# SCH_CyBorg.net
KiCad netlist of a schematic drawn in EasyEDA
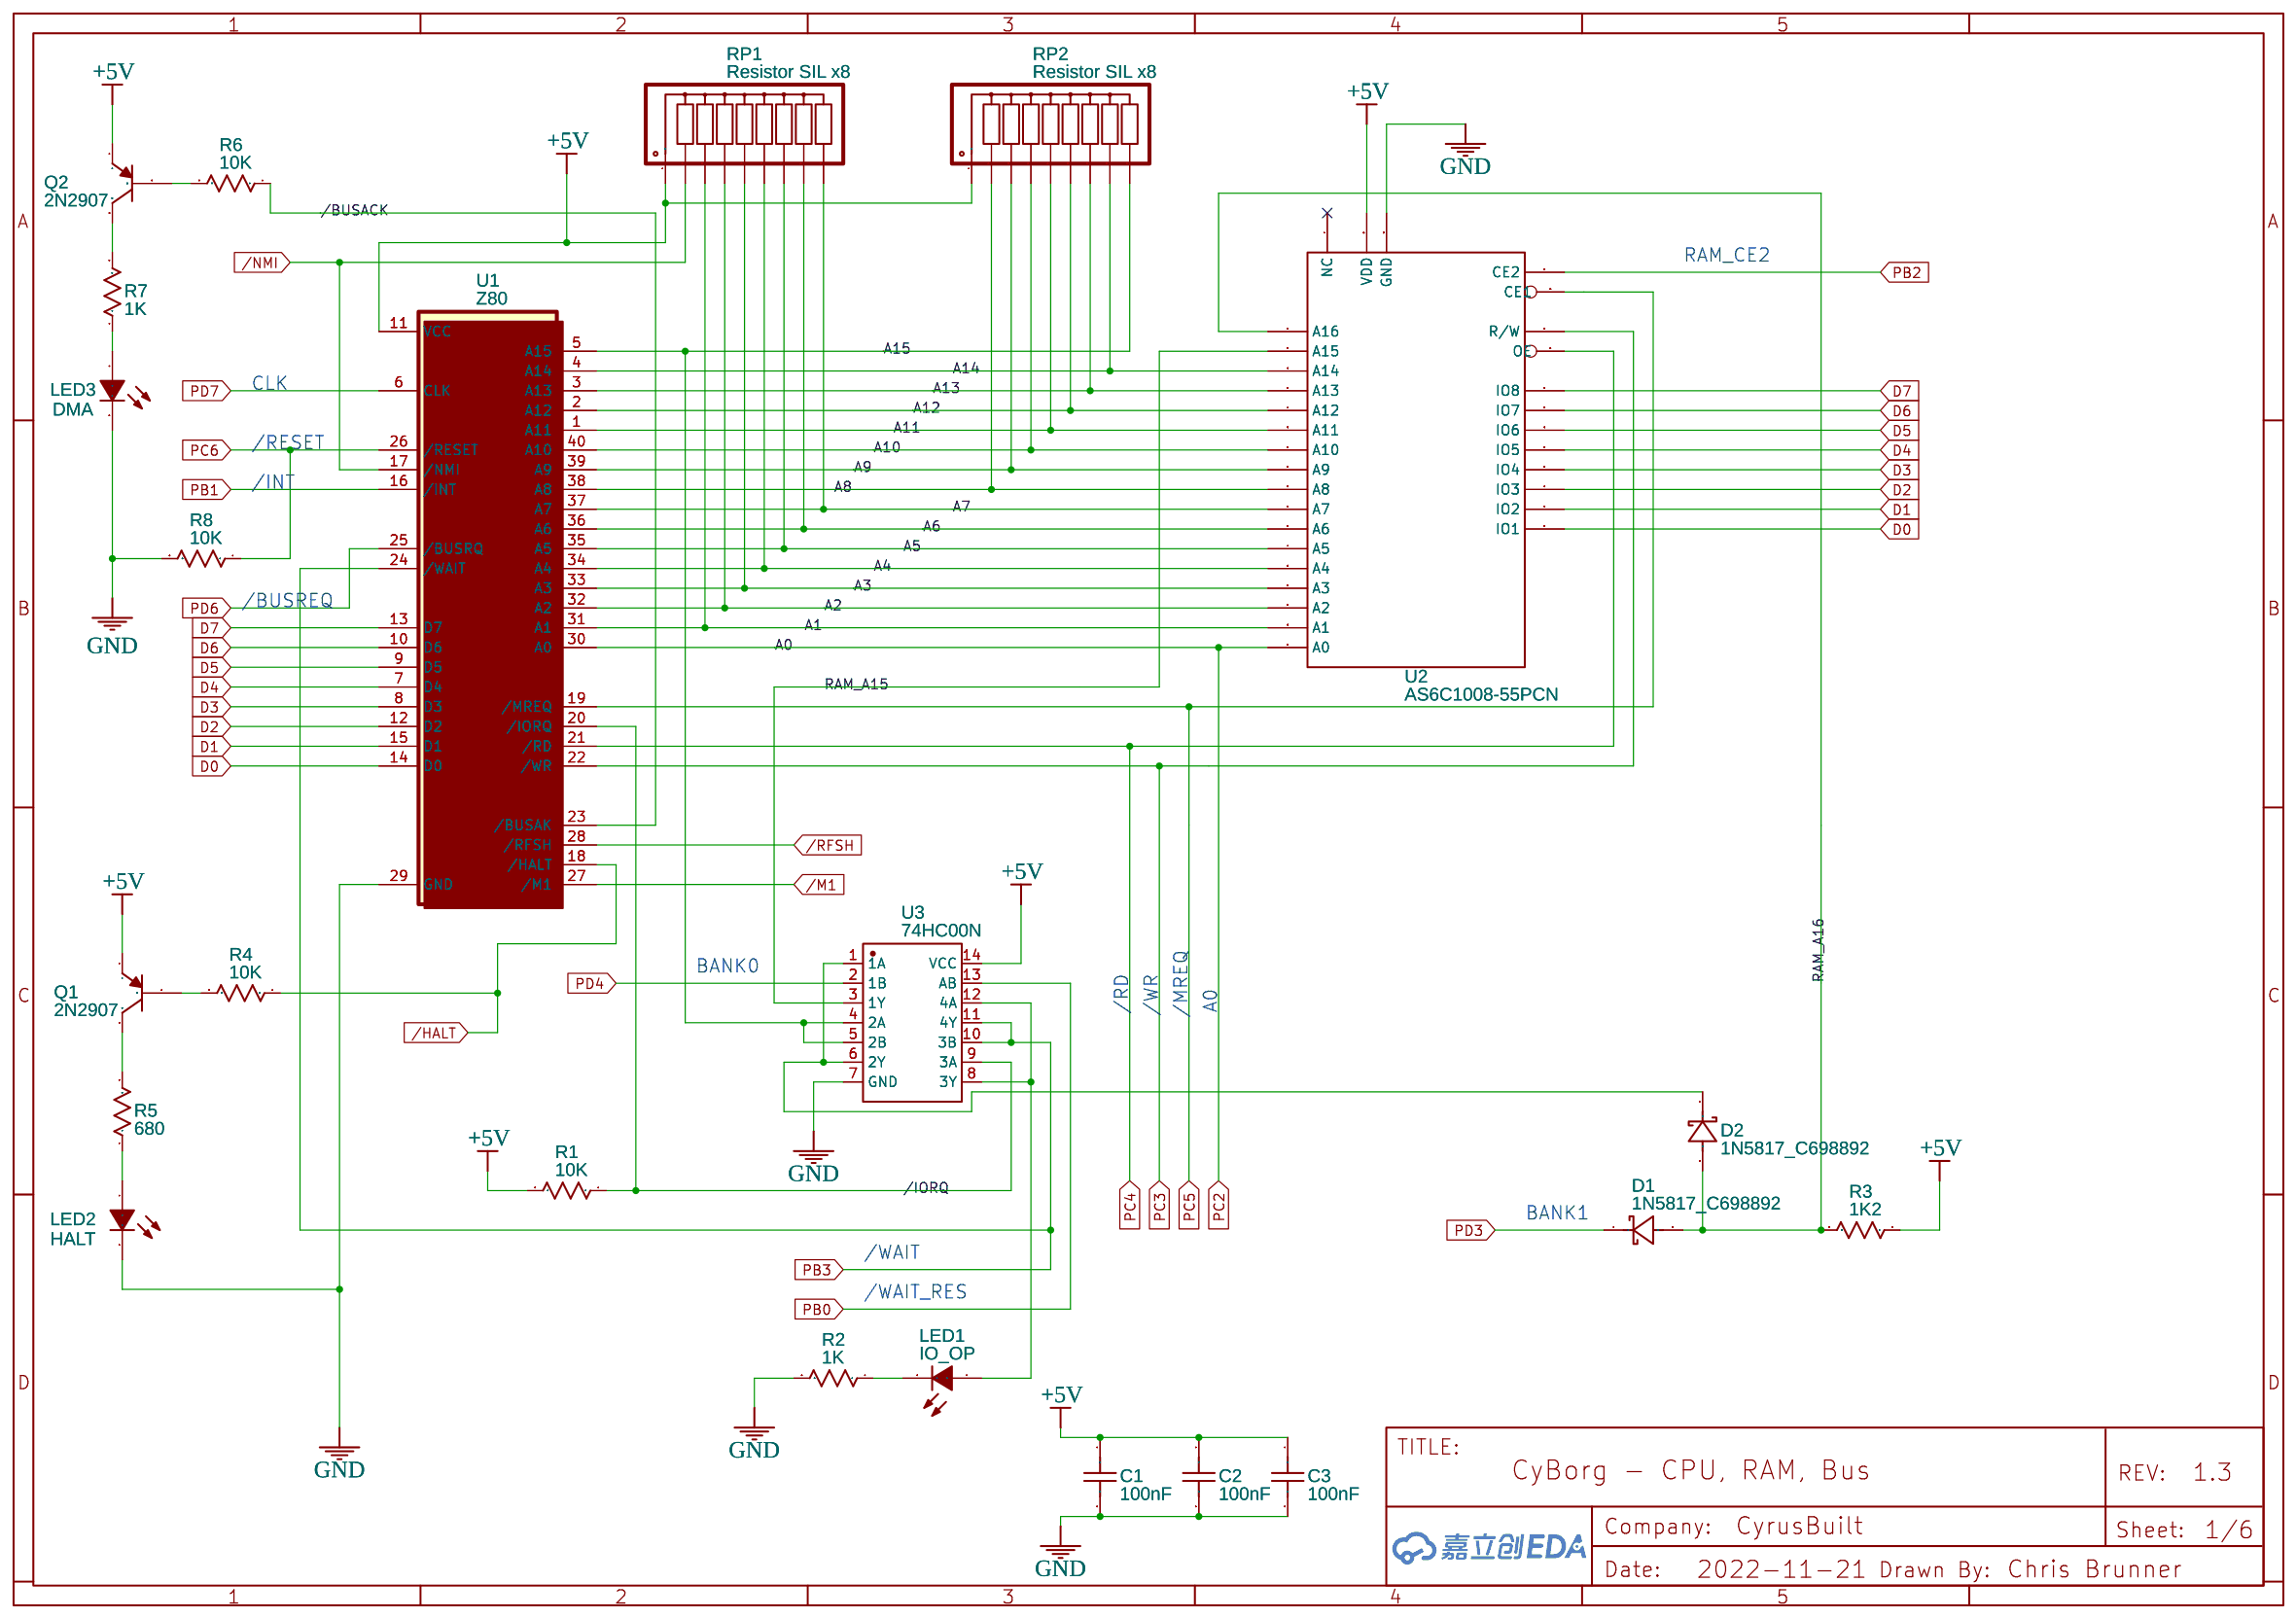
[diagram p0: CPU]
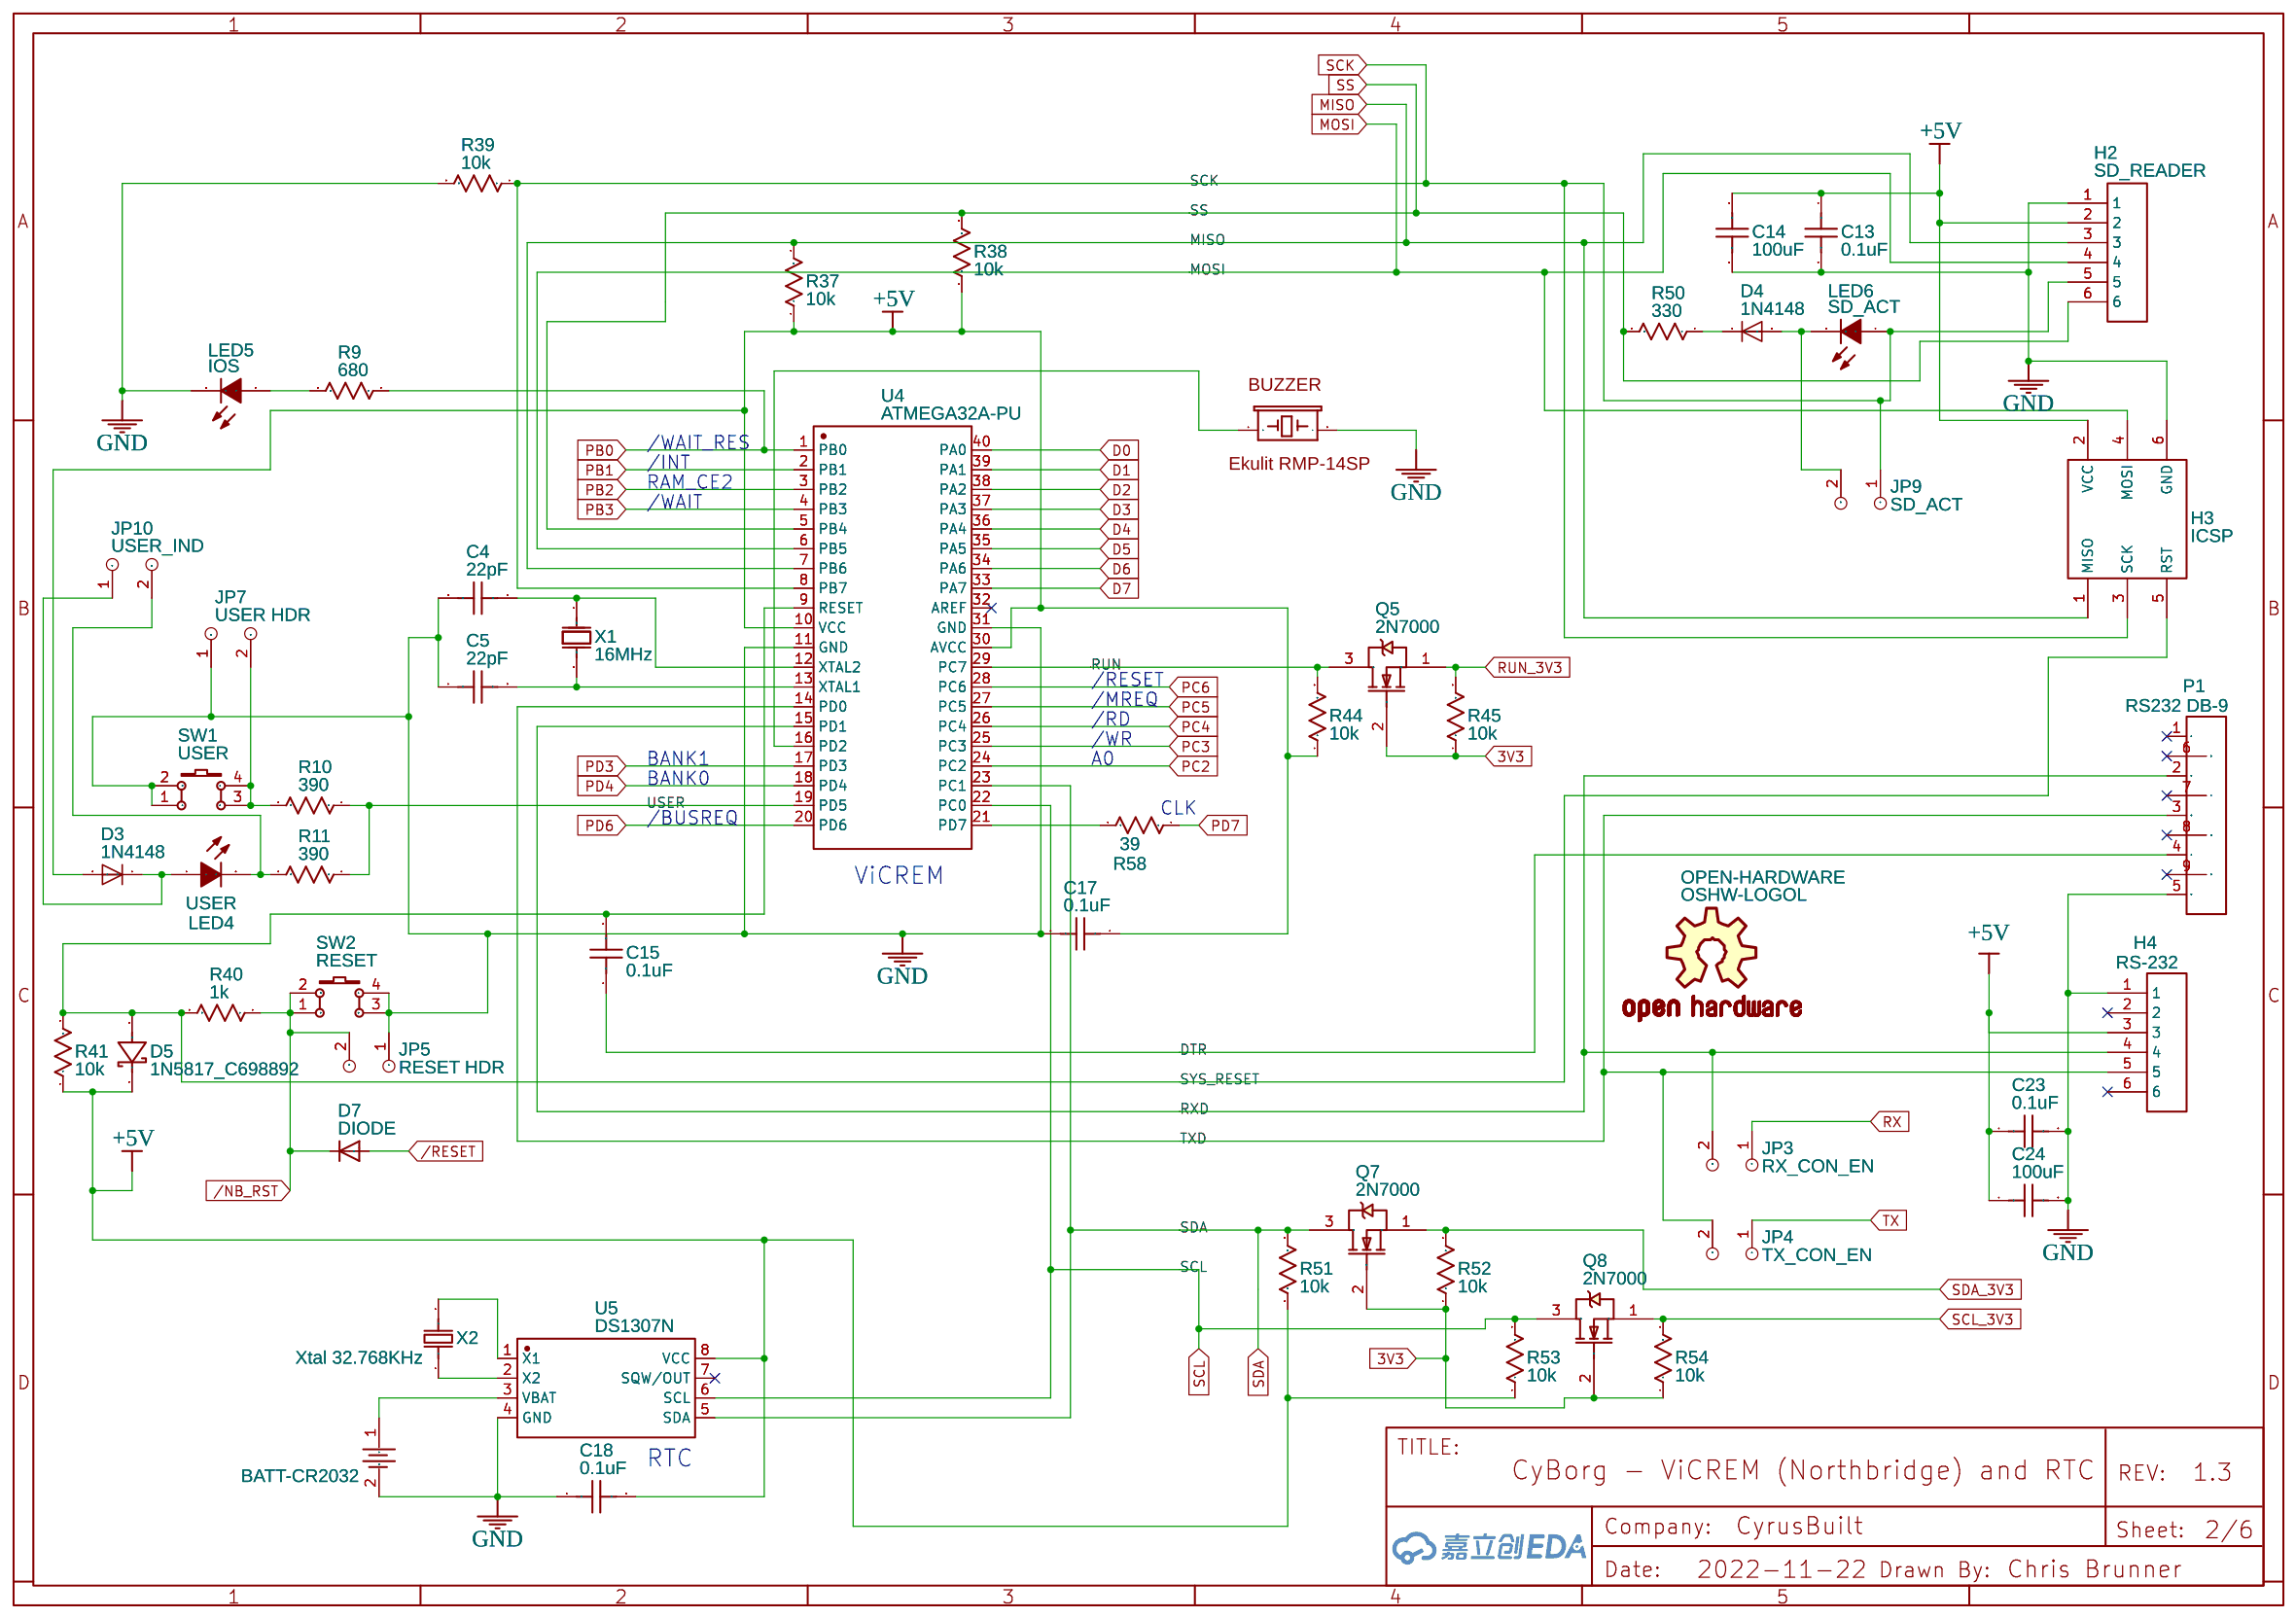
[diagram p1: ViCREM]
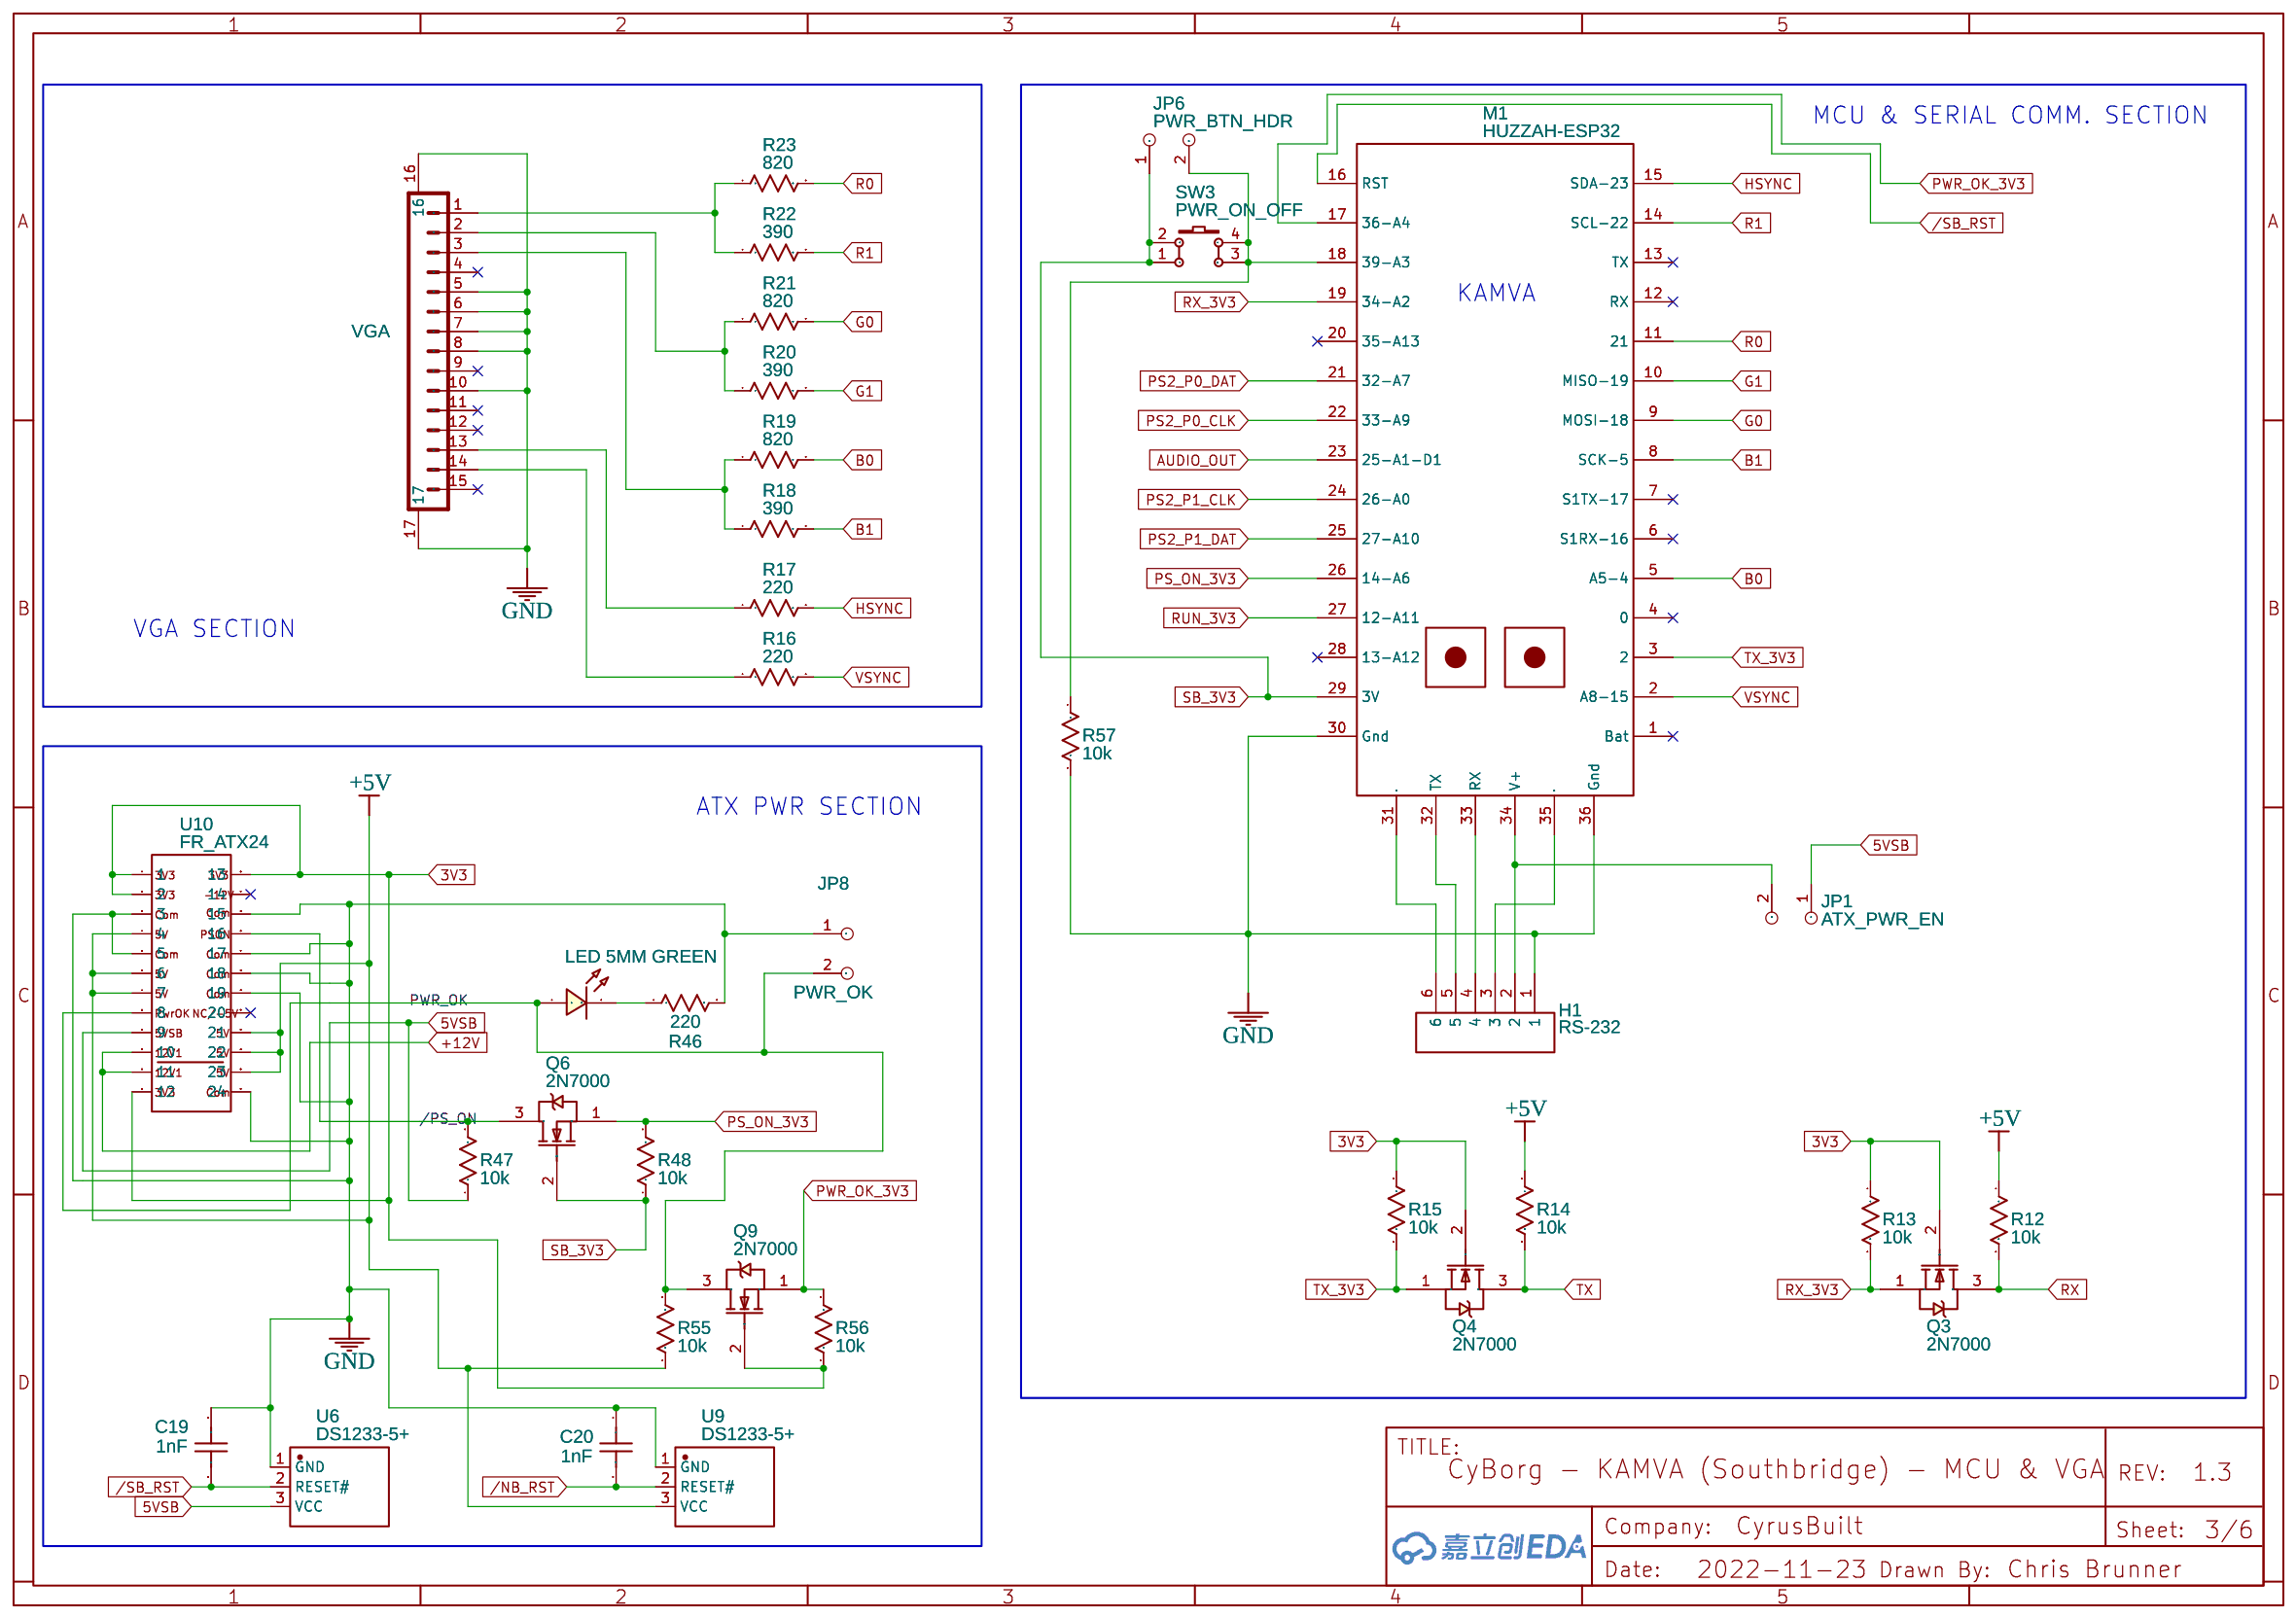
[diagram p2: KAMVA - P1]
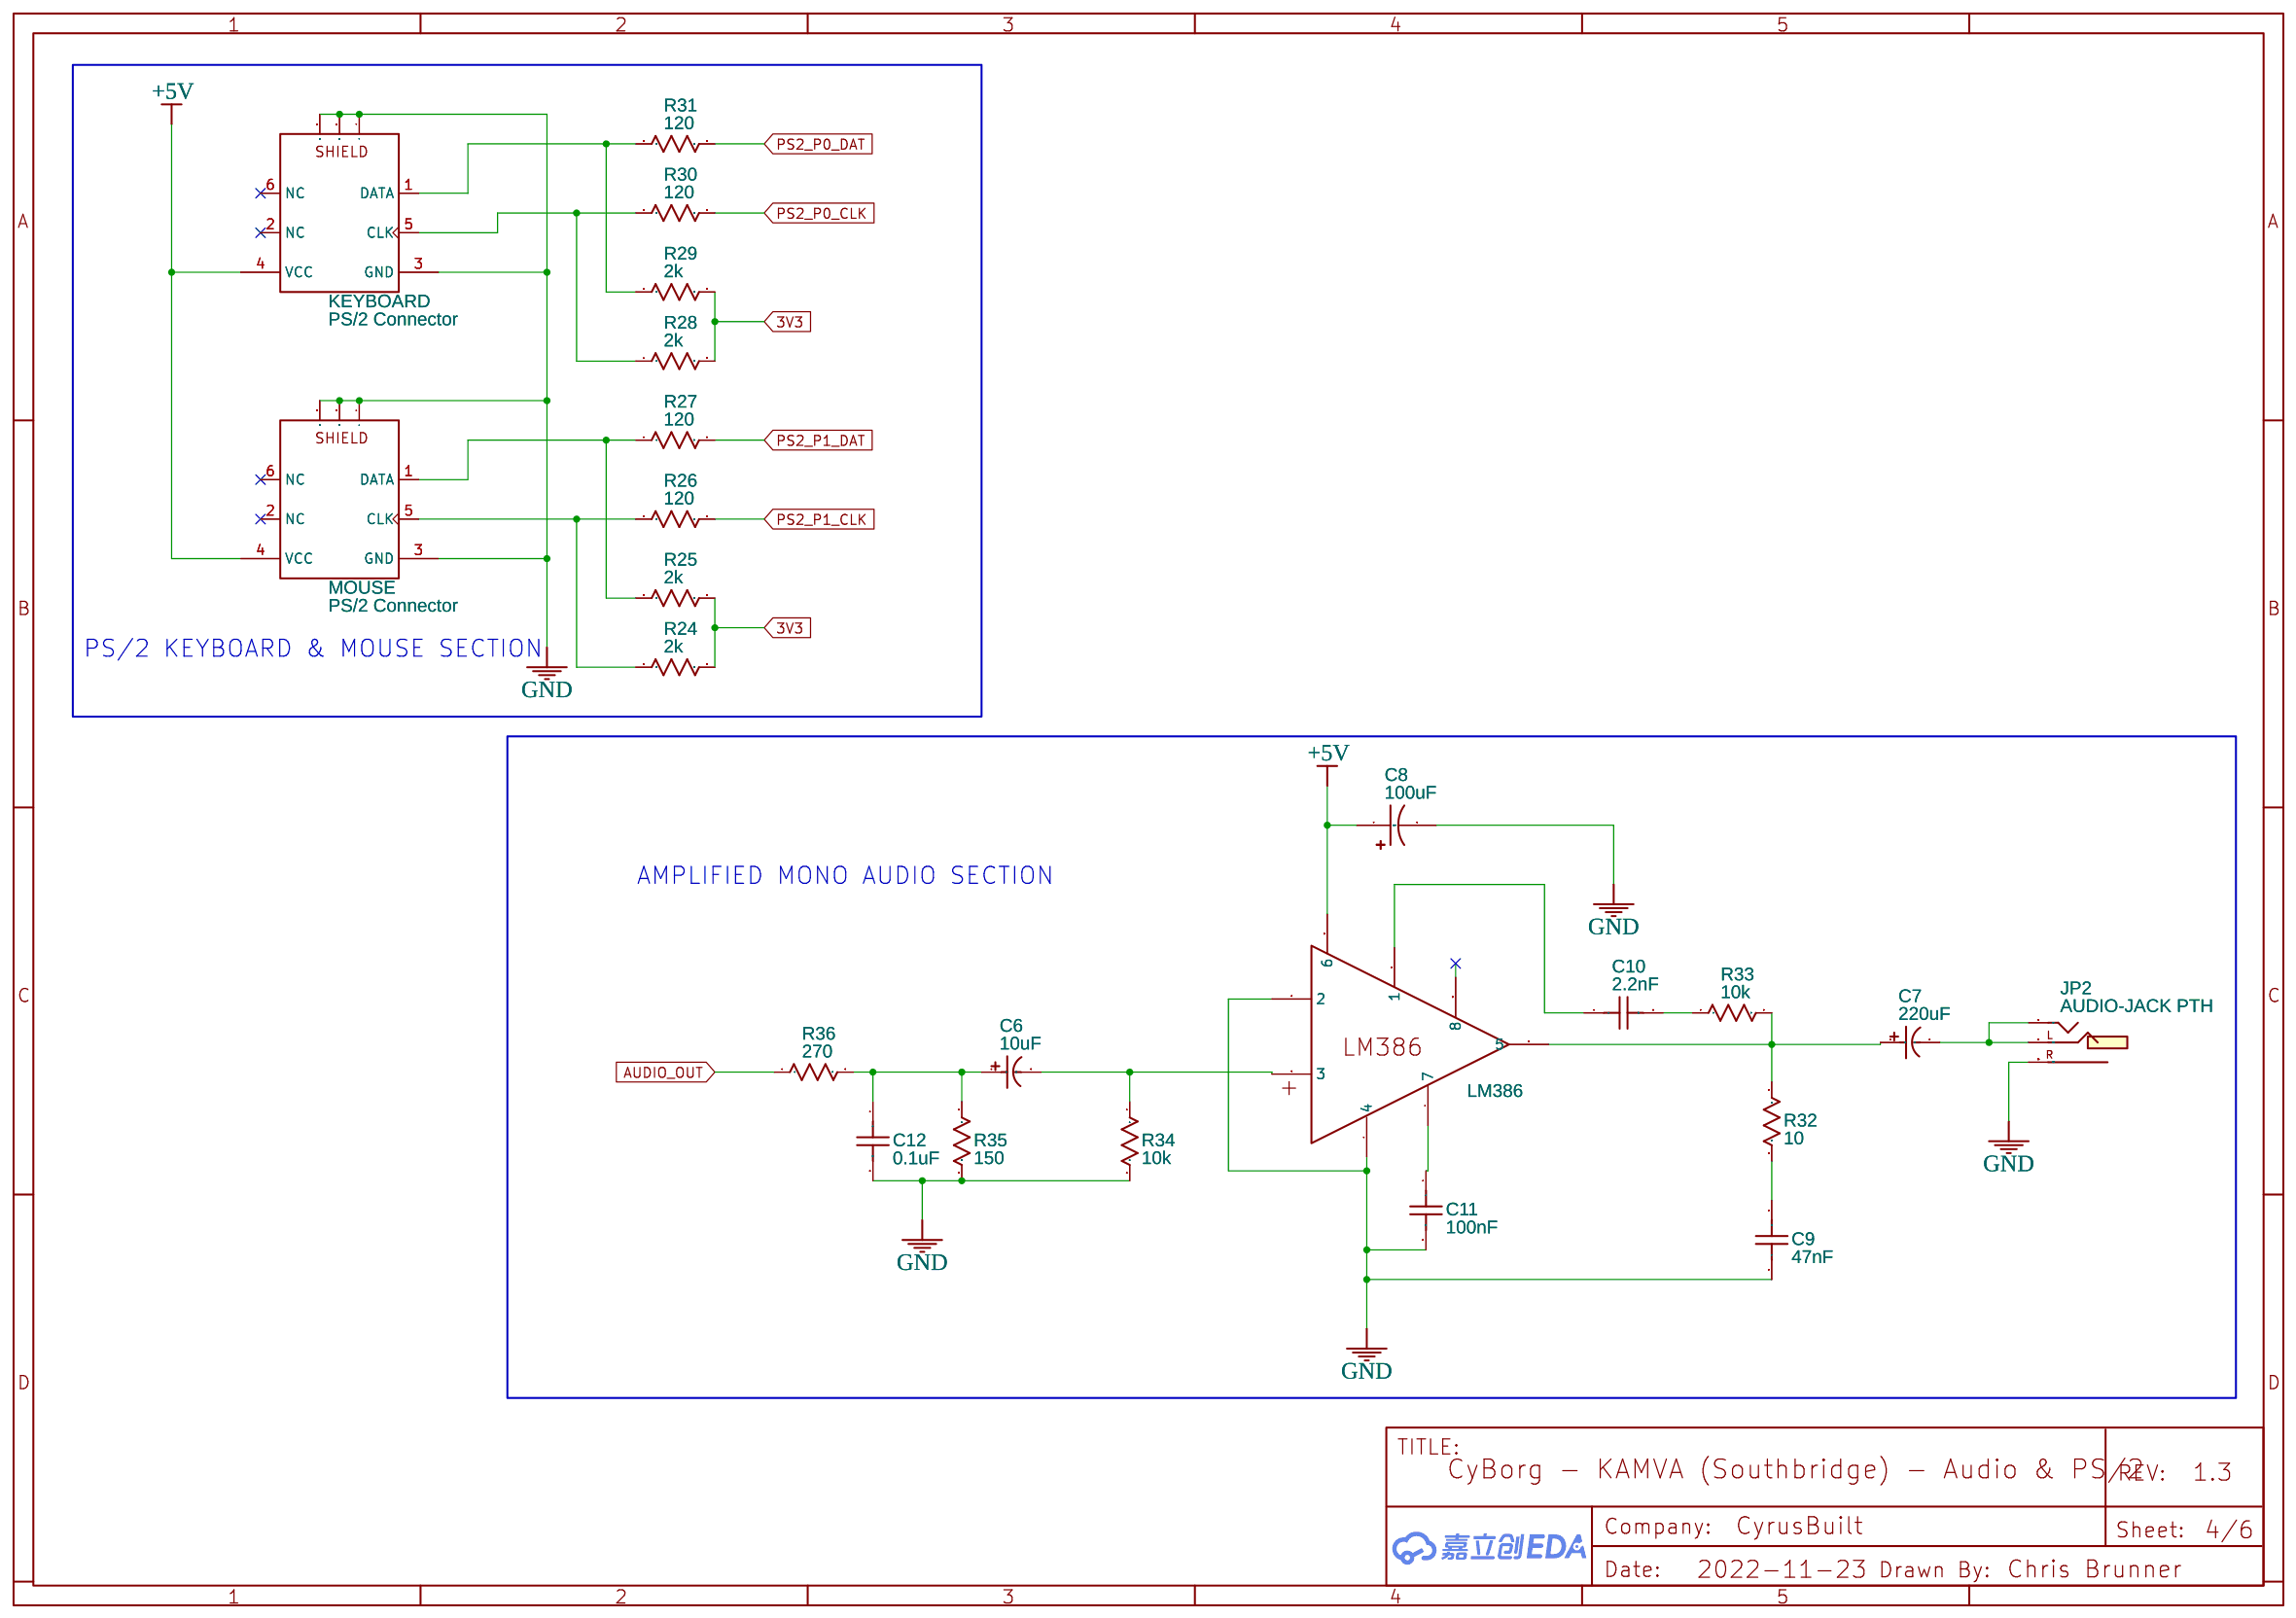
[diagram p3: KAMVA - P2]
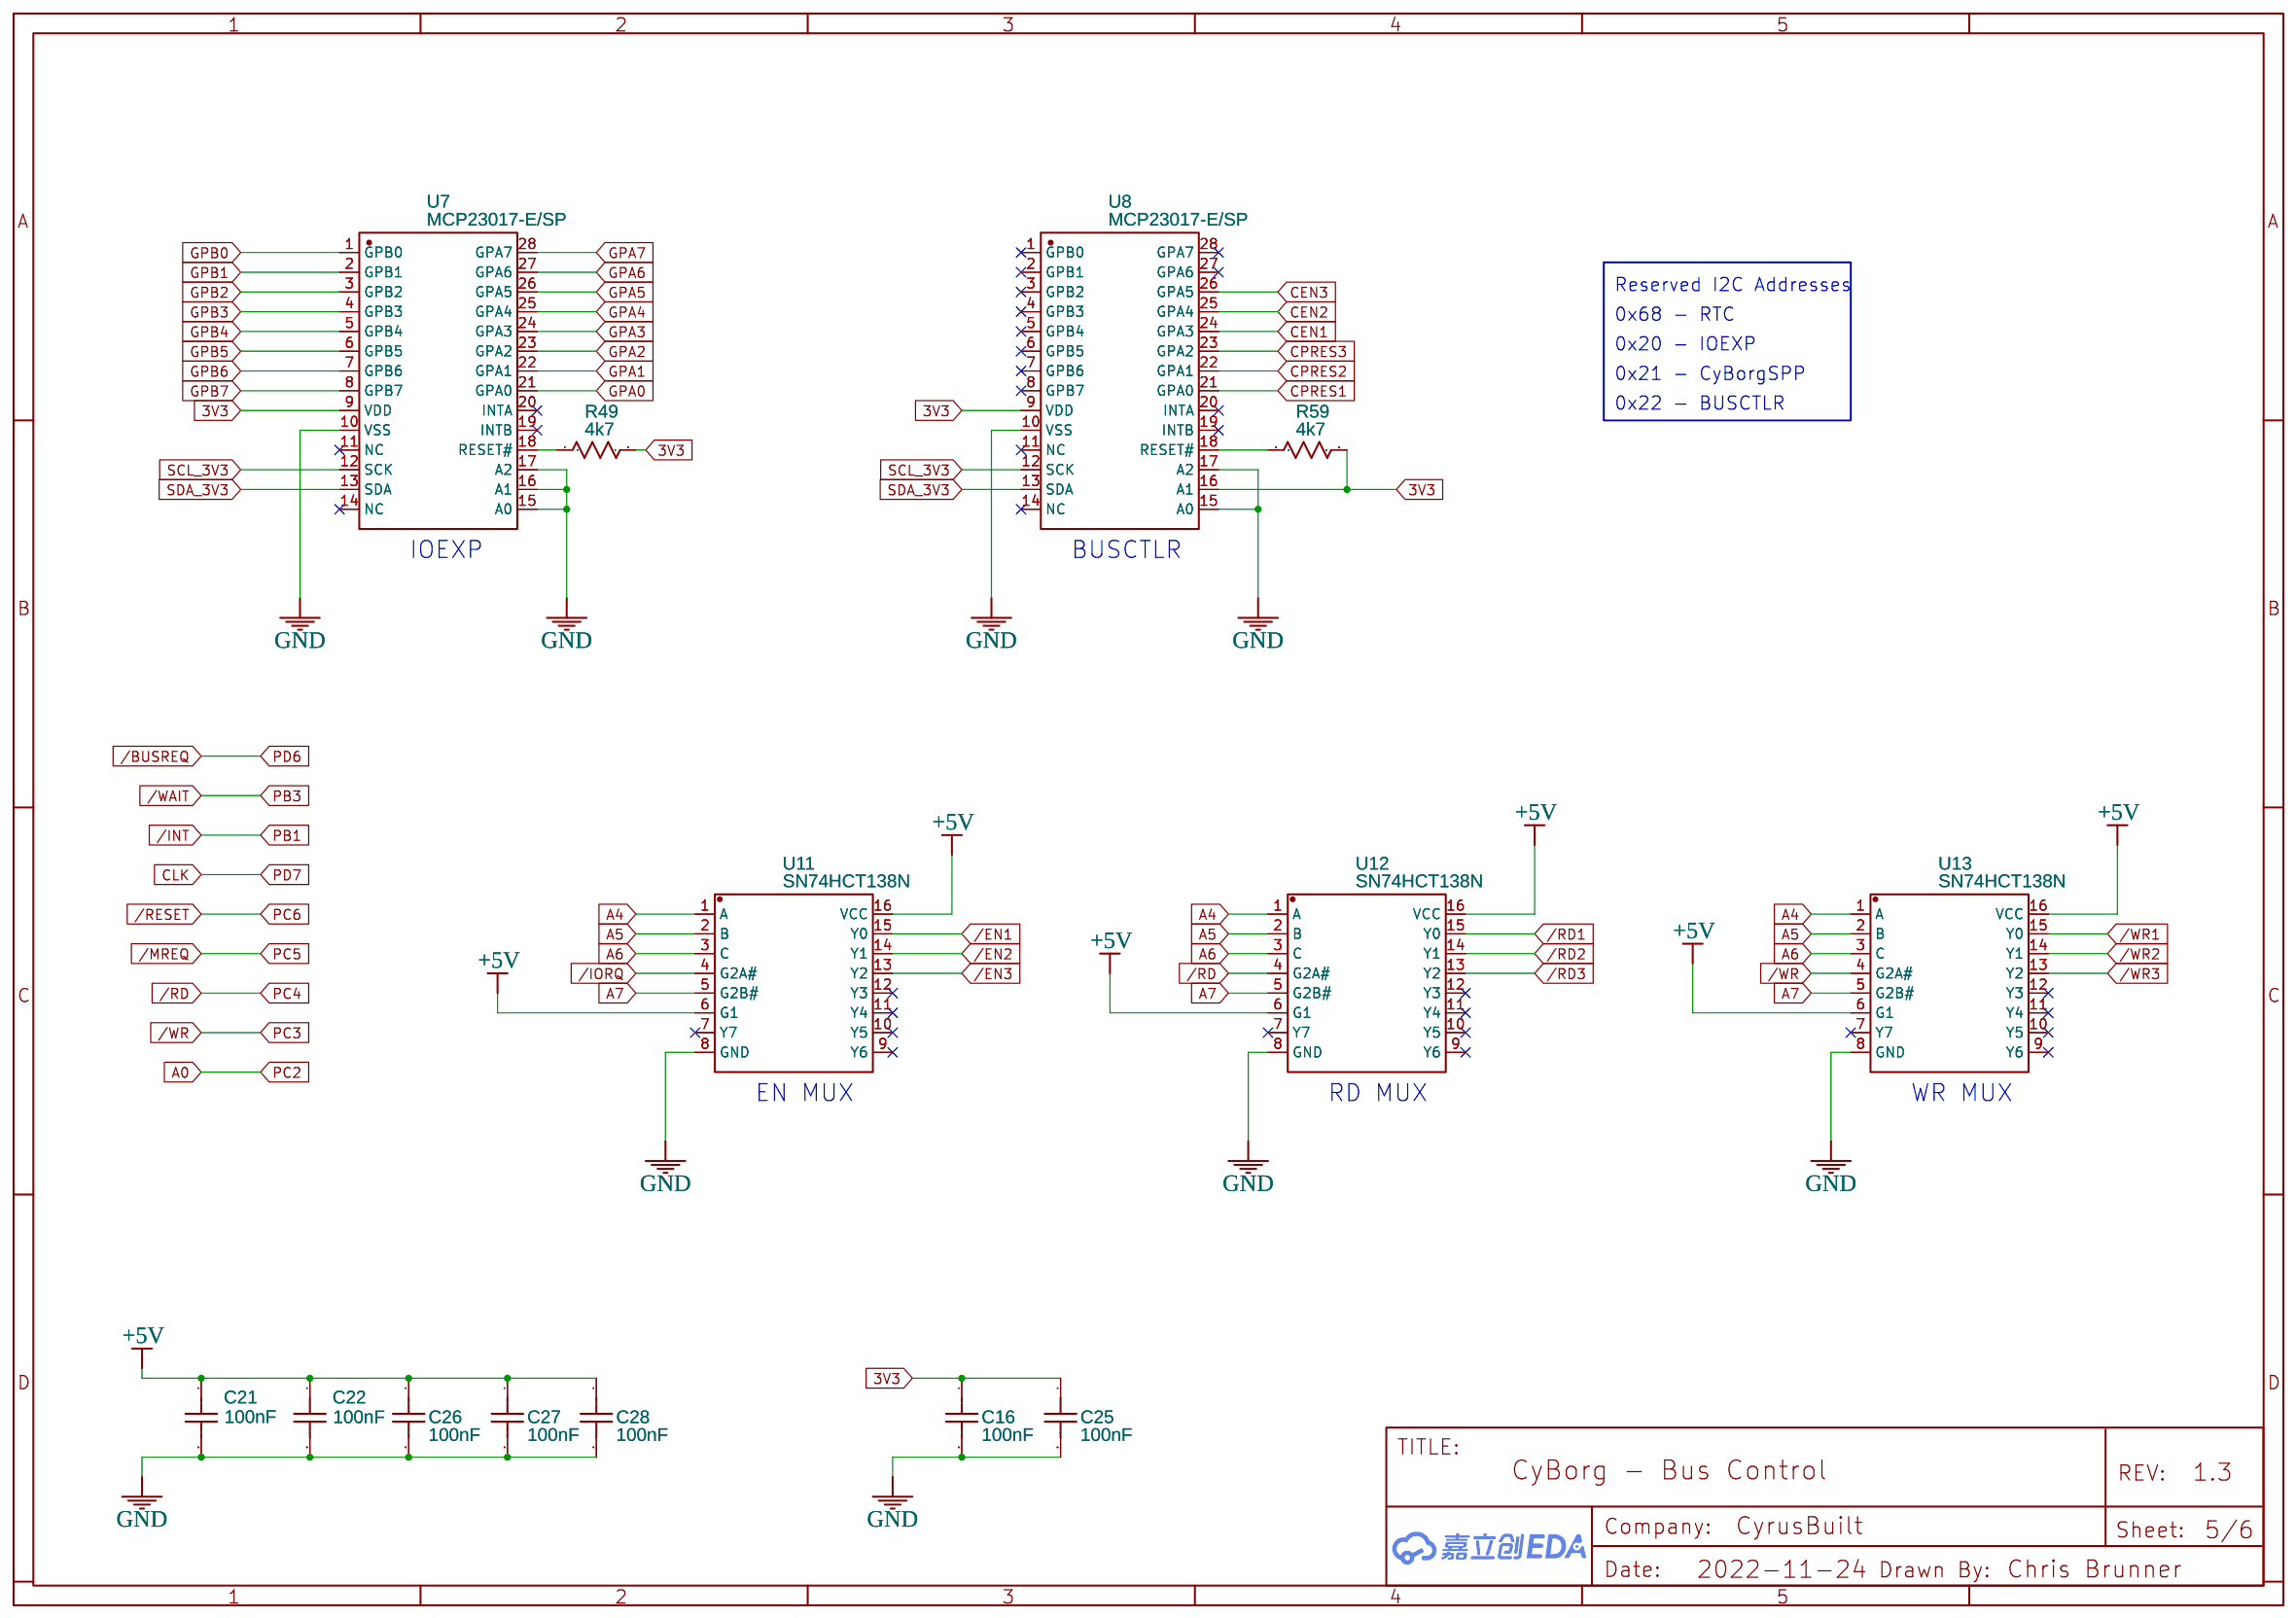
[diagram p4: Bus Control]
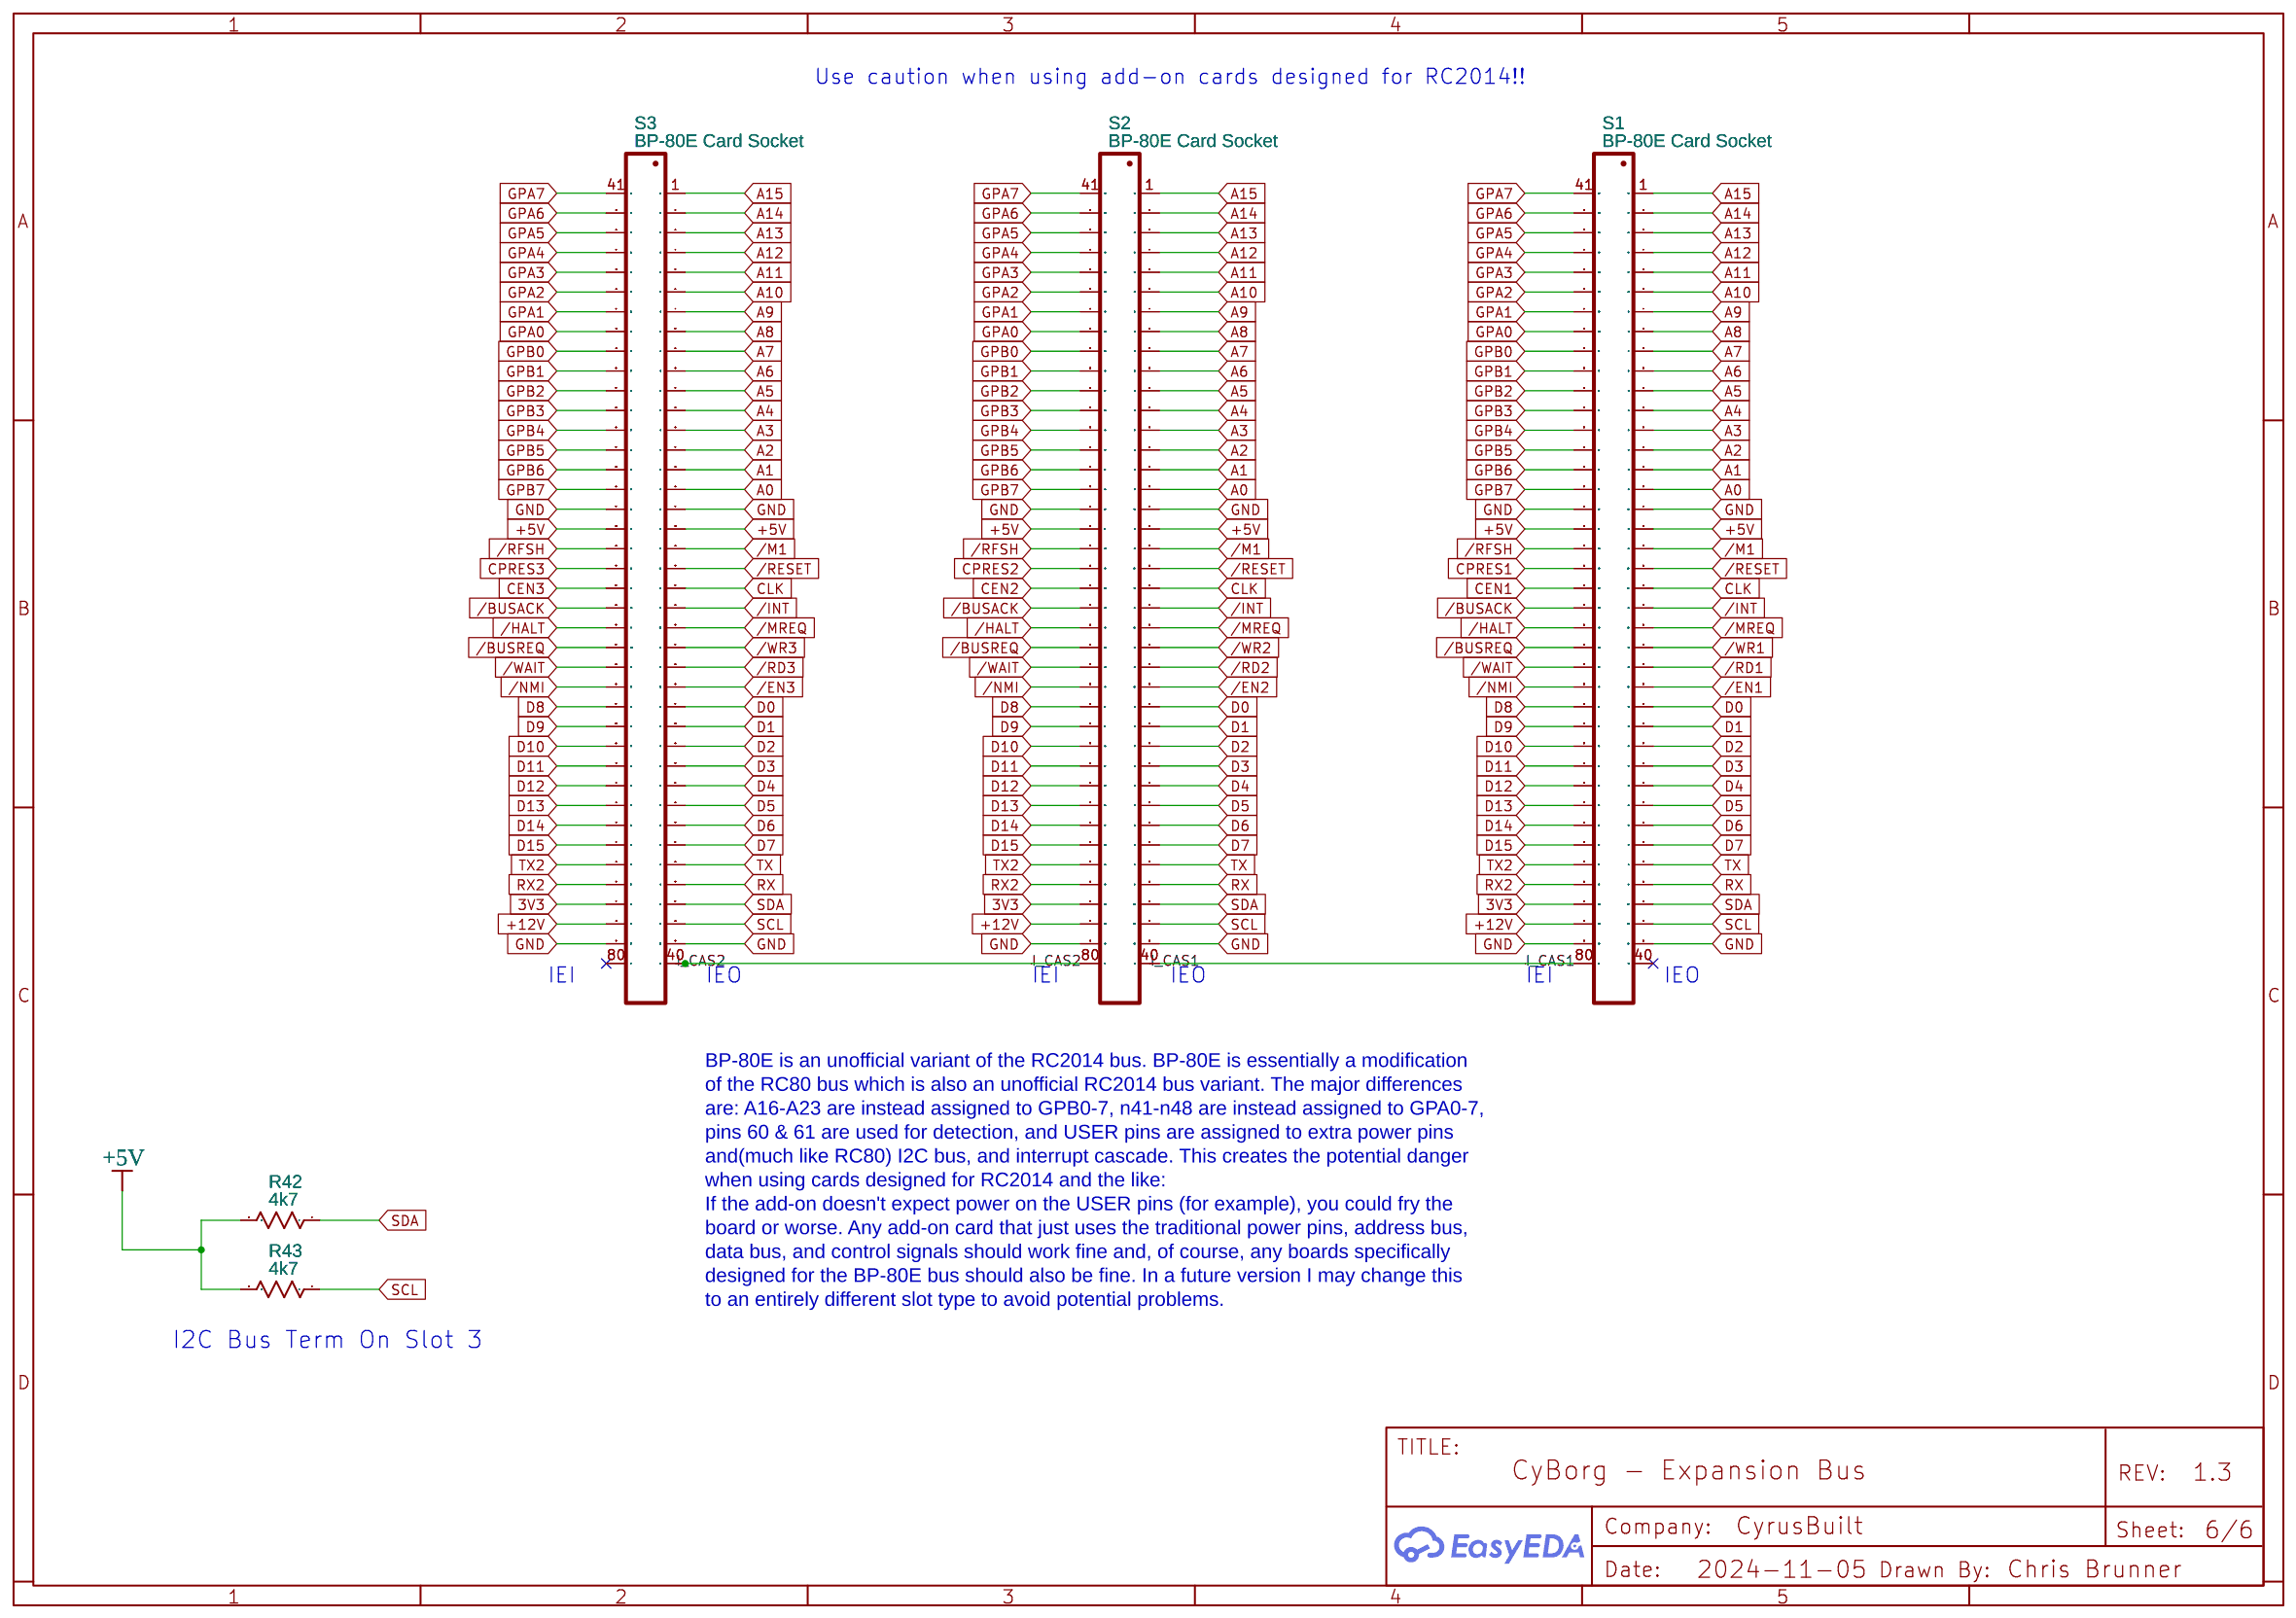
[diagram p5: Expansion Bus]

(export (version "E")
  (design (tool "Eeschema 10.0.6"))
  (components
    (comp (ref "C1") (value "100nF") (libsource (lib "") (part "C_0603_US")))
    (comp (ref "C2") (value "100nF") (libsource (lib "") (part "C_0603_US")))
    (comp (ref "C3") (value "100nF") (libsource (lib "") (part "C_0603_US")))
    (comp (ref "D1")
      (value "1N5817_C698892")
      (fields (field (name "Manufacturer Part") "1N5817") (field (name "Manufacturer") "YANGJIE(扬杰)"))
      (libsource (lib "") (part "1N5817_C698892"))
    )
    (comp (ref "D2")
      (value "1N5817_C698892")
      (fields (field (name "Manufacturer Part") "1N5817") (field (name "Manufacturer") "YANGJIE(扬杰)"))
      (libsource (lib "") (part "1N5817_C698892_1"))
    )
    (comp (ref "LED1")
      (value "IO_OP")
      (fields
        (field (name "Manufacturer Part") "204-10SURD/S530-A3")
        (field (name "Manufacturer") "EVERLIGHT(亿光)")
      )
      (libsource (lib "") (part "204-10SURD/S530-A3"))
    )
    (comp (ref "LED2")
      (value "HALT")
      (fields
        (field (name "Manufacturer Part") "204-10SURD/S530-A3")
        (field (name "Manufacturer") "EVERLIGHT(亿光)")
      )
      (libsource (lib "") (part "204-10SURD/S530-A3_1"))
    )
    (comp (ref "LED3")
      (value "DMA")
      (fields
        (field (name "Manufacturer Part") "204-10SURD/S530-A3")
        (field (name "Manufacturer") "EVERLIGHT(亿光)")
      )
      (libsource (lib "") (part "204-10SURD/S530-A3_1"))
    )
    (comp (ref "Q1")
      (value "2N2907")
      (fields (field (name "Manufacturer Part") "2N2907A") (field (name "Manufacturer") "ST(先科)"))
      (libsource (lib "") (part "2N2907"))
    )
    (comp (ref "Q2")
      (value "2N2907")
      (fields (field (name "Manufacturer Part") "2N2907A") (field (name "Manufacturer") "ST(先科)"))
      (libsource (lib "") (part "2N2907"))
    )
    (comp (ref "R1")
      (value "10K")
      (fields (field (name "Manufacturer Part") "MCF 0.25W 150R") (field (name "Manufacturer") "MULTICOMP"))
      (libsource (lib "") (part "MCF 0.25W 150R"))
    )
    (comp (ref "R2")
      (value "1K")
      (fields (field (name "Manufacturer Part") "MCF 0.25W 1K") (field (name "Manufacturer") "MULTICOMP"))
      (libsource (lib "") (part "MCF 0.25W 150R"))
    )
    (comp (ref "R3")
      (value "1K2")
      (fields (field (name "Manufacturer Part") "MCF 0.25W 150R") (field (name "Manufacturer") "MULTICOMP"))
      (libsource (lib "") (part "MCF 0.25W 150R"))
    )
    (comp (ref "R4")
      (value "10K")
      (fields (field (name "Manufacturer Part") "MCF 0.25W 150R") (field (name "Manufacturer") "MULTICOMP"))
      (libsource (lib "") (part "MCF 0.25W 150R"))
    )
    (comp (ref "R5")
      (value "680")
      (fields (field (name "Manufacturer Part") "MCF 0.25W 150R") (field (name "Manufacturer") "MULTICOMP"))
      (libsource (lib "") (part "MCF 0.25W 150R_1"))
    )
    (comp (ref "R6")
      (value "10K")
      (fields (field (name "Manufacturer Part") "MCF 0.25W 150R") (field (name "Manufacturer") "MULTICOMP"))
      (libsource (lib "") (part "MCF 0.25W 150R"))
    )
    (comp (ref "R7")
      (value "1K")
      (fields (field (name "Manufacturer Part") "MCF 0.25W 150R") (field (name "Manufacturer") "MULTICOMP"))
      (libsource (lib "") (part "MCF 0.25W 150R_1"))
    )
    (comp (ref "R8")
      (value "10K")
      (fields (field (name "Manufacturer Part") "MCF 0.25W 150R") (field (name "Manufacturer") "MULTICOMP"))
      (libsource (lib "") (part "MCF 0.25W 150R"))
    )
    (comp (ref "RP1") (value "Resistor SIL x8") (libsource (lib "") (part "Resistor SIL x8")))
    (comp (ref "RP2") (value "Resistor SIL x8") (libsource (lib "") (part "Resistor SIL x8_1")))
    (comp (ref "U1")
      (value "Z80")
      (fields (field (name "Manufacturer Part") "Z84C0008PEG"))
      (libsource (lib "") (part "Z80"))
    )
    (comp (ref "U2") (value "AS6C1008-55PCN") (libsource (lib "") (part "TC551001BPL")))
    (comp (ref "U3")
      (value "74HC00N")
      (fields (field (name "Manufacturer") "HTC Korea TAEJIN Tech"))
      (libsource (lib "") (part "74HC00N"))
    )
    (comp (ref "C4") (value "22pF") (libsource (lib "") (part "C_0603_US_3")))
    (comp (ref "C5") (value "22pF") (libsource (lib "") (part "C_0603_US")))
    (comp (ref "C13") (value "0.1uF") (libsource (lib "") (part "C_0603_US_2")))
    (comp (ref "C14") (value "100uF") (libsource (lib "") (part "C_0603_US_2")))
    (comp (ref "C15") (value "0.1uF") (libsource (lib "") (part "C_0603_US_1")))
    (comp (ref "C17") (value "0.1uF") (libsource (lib "") (part "C_0603_US_3")))
    (comp (ref "C18") (value "0.1uF") (libsource (lib "") (part "C_0603_US")))
    (comp (ref "C23") (value "0.1uF") (libsource (lib "") (part "C_0603_US")))
    (comp (ref "C24") (value "100uF") (libsource (lib "") (part "C_0603_US")))
    (comp (ref "CR2032") (value "BATT-CR2032") (libsource (lib "") (part "BATT-CR2032")))
    (comp (ref "D3") (value "1N4148") (libsource (lib "") (part "1N4148_1")))
    (comp (ref "D4") (value "1N4148") (libsource (lib "") (part "1N4148")))
    (comp (ref "D5")
      (value "1N5817_C698892")
      (fields (field (name "Manufacturer Part") "1N5817") (field (name "Manufacturer") "YANGJIE(扬杰)"))
      (libsource (lib "") (part "1N5817_C698892"))
    )
    (comp (ref "D7") (value "DIODE") (libsource (lib "") (part "DIODE")))
    (comp (ref "H2") (value "SD_READER") (libsource (lib "") (part "HEADER 1X6")))
    (comp (ref "H3") (value "ICSP") (libsource (lib "") (part "ICSP - 1")))
    (comp (ref "H4") (value "RS-232") (libsource (lib "") (part "HEADER 1X6")))
    (comp (ref "JP3") (value "RX_CON_EN") (libsource (lib "") (part "2 Pin Header_1")))
    (comp (ref "JP4") (value "TX_CON_EN") (libsource (lib "") (part "2 Pin Header_1")))
    (comp (ref "JP5") (value "RESET HDR") (libsource (lib "") (part "2 Pin Header_1")))
    (comp (ref "JP7") (value "USER HDR") (libsource (lib "") (part "2 Pin Header")))
    (comp (ref "JP9") (value "SD_ACT") (libsource (lib "") (part "2 Pin Header_1")))
    (comp (ref "JP10") (value "USER_IND") (libsource (lib "") (part "2 Pin Header")))
    (comp (ref "LED4")
      (value "USER")
      (fields
        (field (name "Manufacturer Part") "204-10SURD/S530-A3")
        (field (name "Manufacturer") "EVERLIGHT(亿光)")
      )
      (libsource (lib "") (part "204-10SURD/S530-A3_1"))
    )
    (comp (ref "LED5")
      (value "IOS")
      (fields
        (field (name "Manufacturer Part") "204-10SURD/S530-A3")
        (field (name "Manufacturer") "EVERLIGHT(亿光)")
      )
      (libsource (lib "") (part "204-10SURD/S530-A3"))
    )
    (comp (ref "LED6")
      (value "SD_ACT")
      (fields
        (field (name "Manufacturer Part") "204-10SURD/S530-A3")
        (field (name "Manufacturer") "EVERLIGHT(亿光)")
      )
      (libsource (lib "") (part "204-10SURD/S530-A3"))
    )
    (comp (ref "OPEN-HARDWARE") (value "OSHW-LOGOL") (libsource (lib "") (part "OSHW-LOGOL")))
    (comp (ref "P1")
      (value "RS232 DB-9")
      (fields (field (name "Manufacturer Part") "RS232DB99pin90度母座"))
      (libsource (lib "") (part "RS232 9 pin Serial connection"))
    )
    (comp (ref "Q5") (value "2N7000") (libsource (lib "") (part "2N7000")))
    (comp (ref "Q7") (value "2N7000") (libsource (lib "") (part "2N7000")))
    (comp (ref "Q8") (value "2N7000") (libsource (lib "") (part "2N7000")))
    (comp (ref "R9")
      (value "680")
      (fields (field (name "Manufacturer Part") "MCF 0.25W 150R") (field (name "Manufacturer") "MULTICOMP"))
      (libsource (lib "") (part "MCF 0.25W 150R_1"))
    )
    (comp (ref "R10")
      (value "390")
      (fields (field (name "Manufacturer Part") "MCF 0.25W 150R") (field (name "Manufacturer") "MULTICOMP"))
      (libsource (lib "") (part "MCF 0.25W 150R_1"))
    )
    (comp (ref "R11")
      (value "390")
      (fields (field (name "Manufacturer Part") "MCF 0.25W 150R") (field (name "Manufacturer") "MULTICOMP"))
      (libsource (lib "") (part "MCF 0.25W 150R_1"))
    )
    (comp (ref "R37")
      (value "10k")
      (fields (field (name "Manufacturer Part") "MCF 0.25W 150R") (field (name "Manufacturer") "MULTICOMP"))
      (libsource (lib "") (part "MCF 0.25W 150R"))
    )
    (comp (ref "R38")
      (value "10k")
      (fields (field (name "Manufacturer Part") "MCF 0.25W 150R") (field (name "Manufacturer") "MULTICOMP"))
      (libsource (lib "") (part "MCF 0.25W 150R"))
    )
    (comp (ref "R39")
      (value "10k")
      (fields (field (name "Manufacturer Part") "MCF 0.25W 150R") (field (name "Manufacturer") "MULTICOMP"))
      (libsource (lib "") (part "MCF 0.25W 150R_1"))
    )
    (comp (ref "R40")
      (value "1k")
      (fields (field (name "Manufacturer Part") "MCF 0.25W 150R") (field (name "Manufacturer") "MULTICOMP"))
      (libsource (lib "") (part "MCF 0.25W 150R_1"))
    )
    (comp (ref "R41")
      (value "10k")
      (fields (field (name "Manufacturer Part") "MCF 0.25W 150R") (field (name "Manufacturer") "MULTICOMP"))
      (libsource (lib "") (part "MCF 0.25W 150R"))
    )
    (comp (ref "R44")
      (value "10k")
      (fields (field (name "Manufacturer Part") "MCF 0.25W 150R") (field (name "Manufacturer") "MULTICOMP"))
      (libsource (lib "") (part "MCF 0.25W 150R"))
    )
    (comp (ref "R45")
      (value "10k")
      (fields (field (name "Manufacturer Part") "MCF 0.25W 150R") (field (name "Manufacturer") "MULTICOMP"))
      (libsource (lib "") (part "MCF 0.25W 150R"))
    )
    (comp (ref "R50")
      (value "330")
      (fields (field (name "Manufacturer Part") "MCF 0.25W 330R") (field (name "Manufacturer") "MULTICOMP"))
      (libsource (lib "") (part "MCF 0.25W 150R_1"))
    )
    (comp (ref "R51")
      (value "10k")
      (fields (field (name "Manufacturer Part") "MCF 0.25W 150R") (field (name "Manufacturer") "MULTICOMP"))
      (libsource (lib "") (part "MCF 0.25W 150R"))
    )
    (comp (ref "R52")
      (value "10k")
      (fields (field (name "Manufacturer Part") "MCF 0.25W 150R") (field (name "Manufacturer") "MULTICOMP"))
      (libsource (lib "") (part "MCF 0.25W 150R"))
    )
    (comp (ref "R53")
      (value "10k")
      (fields (field (name "Manufacturer Part") "MCF 0.25W 150R") (field (name "Manufacturer") "MULTICOMP"))
      (libsource (lib "") (part "MCF 0.25W 150R"))
    )
    (comp (ref "R54")
      (value "10k")
      (fields (field (name "Manufacturer Part") "MCF 0.25W 150R") (field (name "Manufacturer") "MULTICOMP"))
      (libsource (lib "") (part "MCF 0.25W 150R"))
    )
    (comp (ref "R58")
      (value "39")
      (fields (field (name "Manufacturer Part") "MCF 0.25W 330R") (field (name "Manufacturer") "MULTICOMP"))
      (libsource (lib "") (part "MCF 0.25W 150R_1"))
    )
    (comp (ref "SPK")
      (value "BUZZER Ekulit RMP-14SP")
      (fields (field (name "Manufacturer") "Ekulit"))
      (libsource (lib "") (part "BUZZER Ekulit RMP-14SP"))
    )
    (comp (ref "SW1")
      (value "USER")
      (fields (field (name "Manufacturer Part") "K2-1102DP-E4SW-04") (field (name "Manufacturer") "韩国韩荣"))
      (libsource (lib "") (part "K4-6×6_TH"))
    )
    (comp (ref "SW2")
      (value "RESET")
      (fields (field (name "Manufacturer Part") "K2-1102DP-E4SW-04") (field (name "Manufacturer") "韩国韩荣"))
      (libsource (lib "") (part "K4-6×6_TH"))
    )
    (comp (ref "U4")
      (value "ATMEGA32A-PU")
      (fields (field (name "Manufacturer") "MICROCHIP"))
      (libsource (lib "") (part "ATMEGA32A-PU"))
    )
    (comp (ref "U5")
      (value "DS1307N")
      (fields (field (name "Manufacturer") "HGSEMI"))
      (libsource (lib "") (part "DS1307N"))
    )
    (comp (ref "X1")
      (value "16MHz")
      (fields (field (name "Manufacturer Part") "X49SD16MSD2SC") (field (name "Manufacturer") "YXC(扬兴晶振)"))
      (libsource (lib "") (part "X49SD16MSD2SC"))
    )
    (comp (ref "X2") (value "Xtal 32.768KHz") (libsource (lib "") (part "Xtal 32.768KHz")))
    (comp (ref "C19")
      (value "1nF")
      (fields (field (name "Manufacturer Part") "0.1uF/250V"))
      (libsource (lib "") (part "0.1UF/250V"))
    )
    (comp (ref "C20")
      (value "1nF")
      (fields (field (name "Manufacturer Part") "0.1uF/250V"))
      (libsource (lib "") (part "0.1UF/250V"))
    )
    (comp (ref "H1") (value "RS-232") (libsource (lib "") (part "HEADER 1X6")))
    (comp (ref "JP1") (value "ATX_PWR_EN") (libsource (lib "") (part "2 Pin Header")))
    (comp (ref "JP6") (value "PWR_BTN_HDR") (libsource (lib "") (part "2 Pin Header_2")))
    (comp (ref "JP8") (value "PWR_OK") (libsource (lib "") (part "2 Pin Header_1")))
    (comp (ref "LED7") (value "LED 5MM GREEN") (libsource (lib "") (part "LED 5MM GREEN")))
    (comp (ref "M1") (value "HUZZAH-ESP32") (libsource (lib "") (part "HUZZAH-ESP32")))
    (comp (ref "Q3") (value "2N7000") (libsource (lib "") (part "2N7000_1")))
    (comp (ref "Q4") (value "2N7000") (libsource (lib "") (part "2N7000_1")))
    (comp (ref "Q6") (value "2N7000") (libsource (lib "") (part "2N7000")))
    (comp (ref "Q9") (value "2N7000") (libsource (lib "") (part "2N7000")))
    (comp (ref "R12")
      (value "10k")
      (fields (field (name "Manufacturer Part") "MCF 0.25W 150R") (field (name "Manufacturer") "MULTICOMP"))
      (libsource (lib "") (part "MCF 0.25W 150R"))
    )
    (comp (ref "R13")
      (value "10k")
      (fields (field (name "Manufacturer Part") "MCF 0.25W 150R") (field (name "Manufacturer") "MULTICOMP"))
      (libsource (lib "") (part "MCF 0.25W 150R"))
    )
    (comp (ref "R14")
      (value "10k")
      (fields (field (name "Manufacturer Part") "MCF 0.25W 150R") (field (name "Manufacturer") "MULTICOMP"))
      (libsource (lib "") (part "MCF 0.25W 150R"))
    )
    (comp (ref "R15")
      (value "10k")
      (fields (field (name "Manufacturer Part") "MCF 0.25W 150R") (field (name "Manufacturer") "MULTICOMP"))
      (libsource (lib "") (part "MCF 0.25W 150R_2"))
    )
    (comp (ref "R16")
      (value "220")
      (fields (field (name "Manufacturer Part") "MCF 0.25W 150R") (field (name "Manufacturer") "MULTICOMP"))
      (libsource (lib "") (part "MCF 0.25W 150R_1"))
    )
    (comp (ref "R17")
      (value "220")
      (fields (field (name "Manufacturer Part") "MCF 0.25W 150R") (field (name "Manufacturer") "MULTICOMP"))
      (libsource (lib "") (part "MCF 0.25W 150R_1"))
    )
    (comp (ref "R18")
      (value "390")
      (fields (field (name "Manufacturer Part") "MCF 0.25W 150R") (field (name "Manufacturer") "MULTICOMP"))
      (libsource (lib "") (part "MCF 0.25W 150R_1"))
    )
    (comp (ref "R19")
      (value "820")
      (fields (field (name "Manufacturer Part") "MCF 0.25W 150R") (field (name "Manufacturer") "MULTICOMP"))
      (libsource (lib "") (part "MCF 0.25W 150R_1"))
    )
    (comp (ref "R20")
      (value "390")
      (fields (field (name "Manufacturer Part") "MCF 0.25W 150R") (field (name "Manufacturer") "MULTICOMP"))
      (libsource (lib "") (part "MCF 0.25W 150R_1"))
    )
    (comp (ref "R21")
      (value "820")
      (fields (field (name "Manufacturer Part") "MCF 0.25W 150R") (field (name "Manufacturer") "MULTICOMP"))
      (libsource (lib "") (part "MCF 0.25W 150R_1"))
    )
    (comp (ref "R22")
      (value "390")
      (fields (field (name "Manufacturer Part") "MCF 0.25W 150R") (field (name "Manufacturer") "MULTICOMP"))
      (libsource (lib "") (part "MCF 0.25W 150R_1"))
    )
    (comp (ref "R23")
      (value "820")
      (fields (field (name "Manufacturer Part") "MCF 0.25W 150R") (field (name "Manufacturer") "MULTICOMP"))
      (libsource (lib "") (part "MCF 0.25W 150R_1"))
    )
    (comp (ref "R46")
      (value "220")
      (fields (field (name "Manufacturer Part") "MCF 0.25W 150R") (field (name "Manufacturer") "MULTICOMP"))
      (libsource (lib "") (part "MCF 0.25W 150R_1"))
    )
    (comp (ref "R47")
      (value "10k")
      (fields (field (name "Manufacturer Part") "MCF 0.25W 150R") (field (name "Manufacturer") "MULTICOMP"))
      (libsource (lib "") (part "MCF 0.25W 150R_2"))
    )
    (comp (ref "R48")
      (value "10k")
      (fields (field (name "Manufacturer Part") "MCF 0.25W 150R") (field (name "Manufacturer") "MULTICOMP"))
      (libsource (lib "") (part "MCF 0.25W 150R_2"))
    )
    (comp (ref "R55")
      (value "10k")
      (fields (field (name "Manufacturer Part") "MCF 0.25W 150R") (field (name "Manufacturer") "MULTICOMP"))
      (libsource (lib "") (part "MCF 0.25W 150R_2"))
    )
    (comp (ref "R56")
      (value "10k")
      (fields (field (name "Manufacturer Part") "MCF 0.25W 150R") (field (name "Manufacturer") "MULTICOMP"))
      (libsource (lib "") (part "MCF 0.25W 150R_2"))
    )
    (comp (ref "R57")
      (value "10k")
      (fields (field (name "Manufacturer Part") "MCF 0.25W 150R") (field (name "Manufacturer") "MULTICOMP"))
      (libsource (lib "") (part "MCF 0.25W 150R"))
    )
    (comp (ref "SW3")
      (value "PWR_ON_OFF")
      (fields (field (name "Manufacturer Part") "K2-1102DP-E4SW-04") (field (name "Manufacturer") "韩国韩荣"))
      (libsource (lib "") (part "K4-6×6_TH"))
    )
    (comp (ref "U6")
      (value "DS1233-5+")
      (fields
        (field (name "Manufacturer Part") "DS1233-10+")
        (field (name "Manufacturer") "Maxim Integrated")
      )
      (libsource (lib "") (part "DS1233-10+"))
    )
    (comp (ref "U9")
      (value "DS1233-5+")
      (fields
        (field (name "Manufacturer Part") "DS1233-10+")
        (field (name "Manufacturer") "Maxim Integrated")
      )
      (libsource (lib "") (part "DS1233-10+"))
    )
    (comp (ref "U10")
      (value "FR_ATX24")
      (fields (field (name "Manufacturer Part") "ATX-24"))
      (libsource (lib "") (part "FR_ATX24"))
    )
    (comp (ref "VGA")
      (value "VGA-001")
      (fields (field (name "Manufacturer Part") "VGA-002") (field (name "Manufacturer") "BOOMELE(博穆精密)"))
      (libsource (lib "") (part "VGA-002"))
    )
    (comp (ref "C6")
      (value "10uF")
      (fields
        (field (name "Manufacturer Part") "electrolytic capacitor 10UF 50V high frequency")
        (field (name "Manufacturer") "ValuePro")
      )
      (libsource (lib "") (part "electrolytic capacitor"))
    )
    (comp (ref "C7")
      (value "220uF")
      (fields
        (field (name "Manufacturer Part") "Aluminum electrolytic capacitors47uF 63V 20% High frequency green gold")
        (field (name "Manufacturer") "ValuePro")
      )
      (libsource (lib "") (part "220uF"))
    )
    (comp (ref "C8") (value "100uF") (libsource (lib "") (part "100uF")))
    (comp (ref "C9")
      (value "47nF")
      (fields (field (name "Manufacturer Part") "0.1uF/250V"))
      (libsource (lib "") (part "0.1UF/250V"))
    )
    (comp (ref "C10")
      (value "2.2nF")
      (fields (field (name "Manufacturer Part") "0.1uF/250V"))
      (libsource (lib "") (part "0.1UF/250V_1"))
    )
    (comp (ref "C11")
      (value "100nF")
      (fields (field (name "Manufacturer Part") "0.1uF/250V"))
      (libsource (lib "") (part "0.1UF/250V"))
    )
    (comp (ref "C12")
      (value "0.1uF")
      (fields (field (name "Manufacturer Part") "0.1uF/250V"))
      (libsource (lib "") (part "0.1UF/250V"))
    )
    (comp (ref "JP2") (value "AUDIO-JACK PTH") (libsource (lib "") (part "AUDIO-JACKPTH COPY")))
    (comp (ref "KEYBOARD") (value "PS/2 Connector") (libsource (lib "") (part "PS/2 Connector_1")))
    (comp (ref "LM386")
      (value "LM386")
      (fields (field (name "Manufacturer Part") "LM386N-1/NOPB"))
      (libsource (lib "") (part "LM386"))
    )
    (comp (ref "MOUSE") (value "PS/2 Connector") (libsource (lib "") (part "PS/2 Connector")))
    (comp (ref "R24")
      (value "2k")
      (fields (field (name "Manufacturer Part") "MCF 0.25W 150R") (field (name "Manufacturer") "MULTICOMP"))
      (libsource (lib "") (part "MCF 0.25W 150R"))
    )
    (comp (ref "R25")
      (value "2k")
      (fields (field (name "Manufacturer Part") "MCF 0.25W 150R") (field (name "Manufacturer") "MULTICOMP"))
      (libsource (lib "") (part "MCF 0.25W 150R"))
    )
    (comp (ref "R26")
      (value "120")
      (fields (field (name "Manufacturer Part") "MCF 0.25W 150R") (field (name "Manufacturer") "MULTICOMP"))
      (libsource (lib "") (part "MCF 0.25W 150R"))
    )
    (comp (ref "R27")
      (value "120")
      (fields (field (name "Manufacturer Part") "MCF 0.25W 150R") (field (name "Manufacturer") "MULTICOMP"))
      (libsource (lib "") (part "MCF 0.25W 150R"))
    )
    (comp (ref "R28")
      (value "2k")
      (fields (field (name "Manufacturer Part") "MCF 0.25W 150R") (field (name "Manufacturer") "MULTICOMP"))
      (libsource (lib "") (part "MCF 0.25W 150R"))
    )
    (comp (ref "R29")
      (value "2k")
      (fields (field (name "Manufacturer Part") "MCF 0.25W 150R") (field (name "Manufacturer") "MULTICOMP"))
      (libsource (lib "") (part "MCF 0.25W 150R"))
    )
    (comp (ref "R30")
      (value "120")
      (fields (field (name "Manufacturer Part") "MCF 0.25W 150R") (field (name "Manufacturer") "MULTICOMP"))
      (libsource (lib "") (part "MCF 0.25W 150R"))
    )
    (comp (ref "R31")
      (value "120")
      (fields (field (name "Manufacturer Part") "MCF 0.25W 150R") (field (name "Manufacturer") "MULTICOMP"))
      (libsource (lib "") (part "MCF 0.25W 150R"))
    )
    (comp (ref "R32")
      (value "10")
      (fields (field (name "Manufacturer Part") "MCF 0.25W 150R") (field (name "Manufacturer") "MULTICOMP"))
      (libsource (lib "") (part "MCF 0.25W 150R_1"))
    )
    (comp (ref "R33")
      (value "10k")
      (fields (field (name "Manufacturer Part") "MCF 0.25W 150R") (field (name "Manufacturer") "MULTICOMP"))
      (libsource (lib "") (part "MCF 0.25W 150R"))
    )
    (comp (ref "R34")
      (value "10k")
      (fields (field (name "Manufacturer Part") "MCF 0.25W 150R") (field (name "Manufacturer") "MULTICOMP"))
      (libsource (lib "") (part "MCF 0.25W 150R_1"))
    )
    (comp (ref "R35")
      (value "150")
      (fields (field (name "Manufacturer Part") "MCF 0.25W 150R") (field (name "Manufacturer") "MULTICOMP"))
      (libsource (lib "") (part "MCF 0.25W 150R_1"))
    )
    (comp (ref "R36")
      (value "270")
      (fields (field (name "Manufacturer Part") "MCF 0.25W 150R") (field (name "Manufacturer") "MULTICOMP"))
      (libsource (lib "") (part "MCF 0.25W 150R"))
    )
    (comp (ref "C16") (value "100nF") (libsource (lib "") (part "C_0603_US")))
    (comp (ref "C21") (value "100nF") (libsource (lib "") (part "C_0603_US")))
    (comp (ref "C22") (value "100nF") (libsource (lib "") (part "C_0603_US")))
    (comp (ref "C25") (value "100nF") (libsource (lib "") (part "C_0603_US")))
    (comp (ref "C26") (value "100nF") (libsource (lib "") (part "C_0603_US")))
    (comp (ref "C27") (value "100nF") (libsource (lib "") (part "C_0603_US")))
    (comp (ref "C28") (value "100nF") (libsource (lib "") (part "C_0603_US")))
    (comp (ref "R49")
      (value "4k7")
      (fields (field (name "Manufacturer Part") "MCF 0.25W 150R") (field (name "Manufacturer") "MULTICOMP"))
      (libsource (lib "") (part "MCF 0.25W 150R"))
    )
    (comp (ref "R59")
      (value "4k7")
      (fields (field (name "Manufacturer Part") "MCF 0.25W 150R") (field (name "Manufacturer") "MULTICOMP"))
      (libsource (lib "") (part "MCF 0.25W 150R"))
    )
    (comp (ref "U7")
      (value "MCP23017-E/SP")
      (fields (field (name "Manufacturer") "Microchip Tech"))
      (libsource (lib "") (part "MCP23017-E/SP"))
    )
    (comp (ref "U8")
      (value "MCP23017-E/SP")
      (fields (field (name "Manufacturer") "Microchip Tech"))
      (libsource (lib "") (part "MCP23017-E/SP"))
    )
    (comp (ref "U11")
      (value "SN74HCT138N")
      (fields (field (name "Manufacturer") "TI(德州仪器)"))
      (libsource (lib "") (part "SN74HCT138N"))
    )
    (comp (ref "U12")
      (value "SN74HCT138N")
      (fields (field (name "Manufacturer") "TI(德州仪器)"))
      (libsource (lib "") (part "SN74HCT138N"))
    )
    (comp (ref "U13")
      (value "SN74HCT138N")
      (fields (field (name "Manufacturer") "TI(德州仪器)"))
      (libsource (lib "") (part "SN74HCT138N"))
    )
    (comp (ref "R42")
      (value "4k7")
      (fields (field (name "Manufacturer Part") "MCF 0.25W 150R") (field (name "Manufacturer") "MULTICOMP"))
      (libsource (lib "") (part "MCF 0.25W 150R"))
    )
    (comp (ref "R43")
      (value "4k7")
      (fields (field (name "Manufacturer Part") "MCF 0.25W 150R") (field (name "Manufacturer") "MULTICOMP"))
      (libsource (lib "") (part "MCF 0.25W 150R"))
    )
    (comp (ref "S1") (value "BP-80E Card Socket") (libsource (lib "") (part "RC80 Card Socket")))
    (comp (ref "S2") (value "BP-80E Card Socket") (libsource (lib "") (part "RC80 Card Socket")))
    (comp (ref "S3") (value "BP-80E Card Socket") (libsource (lib "") (part "RC80 Card Socket")))
  )
  (nets
    (net (code "1") (name "+5V") (class "Default")
      (node (ref "C1") (pin "1") (pinfunction "1_1") (pintype "unspecified"))
      (node (ref "C13") (pin "1") (pinfunction "1_1") (pintype "unspecified"))
      (node (ref "C14") (pin "1") (pinfunction "1_1") (pintype "unspecified"))
      (node (ref "C17") (pin "1") (pinfunction "1_1") (pintype "unspecified"))
      (node (ref "C18") (pin "2") (pinfunction "2_2") (pintype "unspecified"))
      (node (ref "C2") (pin "1") (pinfunction "1_1") (pintype "unspecified"))
      (node (ref "C21") (pin "1") (pinfunction "1_1") (pintype "unspecified"))
      (node (ref "C22") (pin "1") (pinfunction "1_1") (pintype "unspecified"))
      (node (ref "C23") (pin "1") (pinfunction "1_1") (pintype "unspecified"))
      (node (ref "C24") (pin "1") (pinfunction "1_1") (pintype "unspecified"))
      (node (ref "C26") (pin "1") (pinfunction "1_1") (pintype "unspecified"))
      (node (ref "C27") (pin "1") (pinfunction "1_1") (pintype "unspecified"))
      (node (ref "C28") (pin "1") (pinfunction "1_1") (pintype "unspecified"))
      (node (ref "C3") (pin "1") (pinfunction "1_1") (pintype "unspecified"))
      (node (ref "C8") (pin "1") (pinfunction "1_1") (pintype "unspecified"))
      (node (ref "D3") (pin "2") (pinfunction "A_2") (pintype "unspecified"))
      (node (ref "D5") (pin "1") (pinfunction "1_1") (pintype "unspecified"))
      (node (ref "H2") (pin "2") (pinfunction "2_2") (pintype "unspecified"))
      (node (ref "H3") (pin "2") (pinfunction "VCC_2") (pintype "unspecified"))
      (node (ref "H4") (pin "3") (pinfunction "3_3") (pintype "unspecified"))
      (node (ref "KEYBOARD") (pin "4") (pinfunction "VCC_4") (pintype "unspecified"))
      (node (ref "LM386") (pin "6") (pinfunction "6_6") (pintype "passive"))
      (node (ref "MOUSE") (pin "4") (pinfunction "VCC_4") (pintype "unspecified"))
      (node (ref "Q1") (pin "1") (pinfunction "E_1") (pintype "unspecified"))
      (node (ref "Q2") (pin "1") (pinfunction "E_1") (pintype "unspecified"))
      (node (ref "R1") (pin "2") (pinfunction "2_2") (pintype "unspecified"))
      (node (ref "R12") (pin "1") (pinfunction "1_1") (pintype "unspecified"))
      (node (ref "R14") (pin "1") (pinfunction "1_1") (pintype "unspecified"))
      (node (ref "R3") (pin "1") (pinfunction "1_1") (pintype "unspecified"))
      (node (ref "R37") (pin "1") (pinfunction "1_1") (pintype "unspecified"))
      (node (ref "R38") (pin "1") (pinfunction "1_1") (pintype "unspecified"))
      (node (ref "R41") (pin "1") (pinfunction "1_1") (pintype "unspecified"))
      (node (ref "R42") (pin "2") (pinfunction "2_2") (pintype "unspecified"))
      (node (ref "R43") (pin "2") (pinfunction "2_2") (pintype "unspecified"))
      (node (ref "R44") (pin "1") (pinfunction "1_1") (pintype "unspecified"))
      (node (ref "R51") (pin "1") (pinfunction "1_1") (pintype "unspecified"))
      (node (ref "R53") (pin "1") (pinfunction "1_1") (pintype "unspecified"))
      (node (ref "R55") (pin "1") (pinfunction "1_1") (pintype "unspecified"))
      (node (ref "RP1") (pin "1") (pinfunction "Com_1") (pintype "unspecified"))
      (node (ref "RP2") (pin "1") (pinfunction "Com_1") (pintype "unspecified"))
      (node (ref "S1") (pin "18") (pinfunction "5V_18") (pintype "unspecified"))
      (node (ref "S1") (pin "58") (pinfunction "5V_58") (pintype "unspecified"))
      (node (ref "S2") (pin "18") (pinfunction "5V_18") (pintype "unspecified"))
      (node (ref "S2") (pin "58") (pinfunction "5V_58") (pintype "unspecified"))
      (node (ref "S3") (pin "18") (pinfunction "5V_18") (pintype "unspecified"))
      (node (ref "S3") (pin "58") (pinfunction "5V_58") (pintype "unspecified"))
      (node (ref "U1") (pin "11") (pinfunction "VCC_11") (pintype "unspecified"))
      (node (ref "U10") (pin "21") (pinfunction "21_21") (pintype "unspecified"))
      (node (ref "U10") (pin "22") (pinfunction "22_22") (pintype "unspecified"))
      (node (ref "U10") (pin "23") (pinfunction "23_23") (pintype "unspecified"))
      (node (ref "U10") (pin "4") (pinfunction "4_4") (pintype "unspecified"))
      (node (ref "U10") (pin "6") (pinfunction "6_6") (pintype "unspecified"))
      (node (ref "U10") (pin "7") (pinfunction "7_7") (pintype "unspecified"))
      (node (ref "U11") (pin "16") (pinfunction "VCC_16") (pintype "unspecified"))
      (node (ref "U11") (pin "6") (pinfunction "G1_6") (pintype "unspecified"))
      (node (ref "U12") (pin "16") (pinfunction "VCC_16") (pintype "unspecified"))
      (node (ref "U12") (pin "6") (pinfunction "G1_6") (pintype "unspecified"))
      (node (ref "U13") (pin "16") (pinfunction "VCC_16") (pintype "unspecified"))
      (node (ref "U13") (pin "6") (pinfunction "G1_6") (pintype "unspecified"))
      (node (ref "U2") (pin "32") (pinfunction "VDD_32") (pintype "passive"))
      (node (ref "U3") (pin "14") (pinfunction "VCC_14") (pintype "unspecified"))
      (node (ref "U4") (pin "10") (pinfunction "VCC_10") (pintype "unspecified"))
      (node (ref "U4") (pin "30") (pinfunction "AVCC_30") (pintype "unspecified"))
      (node (ref "U5") (pin "8") (pinfunction "VCC_8") (pintype "unspecified"))
      (node (ref "U9") (pin "3") (pinfunction "VCC_3") (pintype "unspecified"))
    )
    (net (code "2") (name "+12V") (class "Default")
      (node (ref "S1") (pin "78") (pinfunction "USR6_78") (pintype "unspecified"))
      (node (ref "S2") (pin "78") (pinfunction "USR6_78") (pintype "unspecified"))
      (node (ref "S3") (pin "78") (pinfunction "USR6_78") (pintype "unspecified"))
      (node (ref "U10") (pin "10") (pinfunction "10_10") (pintype "unspecified"))
      (node (ref "U10") (pin "11") (pinfunction "11_11") (pintype "unspecified"))
    )
    (net (code "3") (name "3V3") (class "Default")
      (node (ref "C16") (pin "1") (pinfunction "1_1") (pintype "unspecified"))
      (node (ref "C25") (pin "1") (pinfunction "1_1") (pintype "unspecified"))
      (node (ref "Q3") (pin "2") (pinfunction "G_2") (pintype "unspecified"))
      (node (ref "Q4") (pin "2") (pinfunction "G_2") (pintype "unspecified"))
      (node (ref "Q5") (pin "2") (pinfunction "G_2") (pintype "unspecified"))
      (node (ref "Q7") (pin "2") (pinfunction "G_2") (pintype "unspecified"))
      (node (ref "Q8") (pin "2") (pinfunction "G_2") (pintype "unspecified"))
      (node (ref "Q9") (pin "2") (pinfunction "G_2") (pintype "unspecified"))
      (node (ref "R13") (pin "1") (pinfunction "1_1") (pintype "unspecified"))
      (node (ref "R15") (pin "2") (pinfunction "2_2") (pintype "unspecified"))
      (node (ref "R24") (pin "2") (pinfunction "2_2") (pintype "unspecified"))
      (node (ref "R25") (pin "2") (pinfunction "2_2") (pintype "unspecified"))
      (node (ref "R28") (pin "2") (pinfunction "2_2") (pintype "unspecified"))
      (node (ref "R29") (pin "2") (pinfunction "2_2") (pintype "unspecified"))
      (node (ref "R45") (pin "1") (pinfunction "1_1") (pintype "unspecified"))
      (node (ref "R49") (pin "2") (pinfunction "2_2") (pintype "unspecified"))
      (node (ref "R52") (pin "1") (pinfunction "1_1") (pintype "unspecified"))
      (node (ref "R54") (pin "1") (pinfunction "1_1") (pintype "unspecified"))
      (node (ref "R56") (pin "1") (pinfunction "1_1") (pintype "unspecified"))
      (node (ref "R59") (pin "2") (pinfunction "2_2") (pintype "unspecified"))
      (node (ref "S1") (pin "77") (pinfunction "USR5_77") (pintype "unspecified"))
      (node (ref "S2") (pin "77") (pinfunction "USR5_77") (pintype "unspecified"))
      (node (ref "S3") (pin "77") (pinfunction "USR5_77") (pintype "unspecified"))
      (node (ref "U10") (pin "1") (pinfunction "1_1") (pintype "unspecified"))
      (node (ref "U10") (pin "12") (pinfunction "12_12") (pintype "unspecified"))
      (node (ref "U10") (pin "13") (pinfunction "13_13") (pintype "unspecified"))
      (node (ref "U10") (pin "2") (pinfunction "2_2") (pintype "unspecified"))
      (node (ref "U7") (pin "9") (pinfunction "VDD_9") (pintype "unspecified"))
      (node (ref "U8") (pin "16") (pinfunction "A1_16") (pintype "unspecified"))
      (node (ref "U8") (pin "9") (pinfunction "VDD_9") (pintype "unspecified"))
    )
    (net (code "4") (name "5VSB") (class "Default")
      (node (ref "JP1") (pin "1") (pinfunction "1_1") (pintype "unspecified"))
      (node (ref "R47") (pin "1") (pinfunction "1_1") (pintype "unspecified"))
      (node (ref "U10") (pin "9") (pinfunction "9_9") (pintype "unspecified"))
      (node (ref "U6") (pin "3") (pinfunction "VCC_3") (pintype "unspecified"))
    )
    (net (code "5") (name "A0") (class "Default")
      (node (ref "S1") (pin "16") (pinfunction "A0_16") (pintype "unspecified"))
      (node (ref "S2") (pin "16") (pinfunction "A0_16") (pintype "unspecified"))
      (node (ref "S3") (pin "16") (pinfunction "A0_16") (pintype "unspecified"))
      (node (ref "U1") (pin "30") (pinfunction "A0_30") (pintype "unspecified"))
      (node (ref "U2") (pin "11") (pinfunction "A0_11") (pintype "input"))
      (node (ref "U4") (pin "24") (pinfunction "PC2_24") (pintype "unspecified"))
    )
    (net (code "6") (name "A1") (class "Default")
      (node (ref "RP1") (pin "3") (pintype "unspecified"))
      (node (ref "S1") (pin "15") (pinfunction "A1_15") (pintype "unspecified"))
      (node (ref "S2") (pin "15") (pinfunction "A1_15") (pintype "unspecified"))
      (node (ref "S3") (pin "15") (pinfunction "A1_15") (pintype "unspecified"))
      (node (ref "U1") (pin "31") (pinfunction "A1_31") (pintype "unspecified"))
      (node (ref "U2") (pin "10") (pinfunction "A1_10") (pintype "input"))
    )
    (net (code "7") (name "A2") (class "Default")
      (node (ref "RP1") (pin "4") (pintype "unspecified"))
      (node (ref "S1") (pin "14") (pinfunction "A2_14") (pintype "unspecified"))
      (node (ref "S2") (pin "14") (pinfunction "A2_14") (pintype "unspecified"))
      (node (ref "S3") (pin "14") (pinfunction "A2_14") (pintype "unspecified"))
      (node (ref "U1") (pin "32") (pinfunction "A2_32") (pintype "unspecified"))
      (node (ref "U2") (pin "9") (pinfunction "A2_9") (pintype "input"))
    )
    (net (code "8") (name "A3") (class "Default")
      (node (ref "RP1") (pin "5") (pintype "unspecified"))
      (node (ref "S1") (pin "13") (pinfunction "A3_13") (pintype "unspecified"))
      (node (ref "S2") (pin "13") (pinfunction "A3_13") (pintype "unspecified"))
      (node (ref "S3") (pin "13") (pinfunction "A3_13") (pintype "unspecified"))
      (node (ref "U1") (pin "33") (pinfunction "A3_33") (pintype "unspecified"))
      (node (ref "U2") (pin "15") (pinfunction "A3_15") (pintype "input"))
    )
    (net (code "9") (name "A4") (class "Default")
      (node (ref "RP1") (pin "6") (pintype "unspecified"))
      (node (ref "S1") (pin "12") (pinfunction "A4_12") (pintype "unspecified"))
      (node (ref "S2") (pin "12") (pinfunction "A4_12") (pintype "unspecified"))
      (node (ref "S3") (pin "12") (pinfunction "A4_12") (pintype "unspecified"))
      (node (ref "U1") (pin "34") (pinfunction "A4_34") (pintype "unspecified"))
      (node (ref "U11") (pin "1") (pinfunction "A_1") (pintype "unspecified"))
      (node (ref "U12") (pin "1") (pinfunction "A_1") (pintype "unspecified"))
      (node (ref "U13") (pin "1") (pinfunction "A_1") (pintype "unspecified"))
      (node (ref "U2") (pin "8") (pinfunction "A4_8") (pintype "input"))
    )
    (net (code "10") (name "A5") (class "Default")
      (node (ref "RP1") (pin "7") (pintype "unspecified"))
      (node (ref "S1") (pin "11") (pinfunction "A5_11") (pintype "unspecified"))
      (node (ref "S2") (pin "11") (pinfunction "A5_11") (pintype "unspecified"))
      (node (ref "S3") (pin "11") (pinfunction "A5_11") (pintype "unspecified"))
      (node (ref "U1") (pin "35") (pinfunction "A5_35") (pintype "unspecified"))
      (node (ref "U11") (pin "2") (pinfunction "B_2") (pintype "unspecified"))
      (node (ref "U12") (pin "2") (pinfunction "B_2") (pintype "unspecified"))
      (node (ref "U13") (pin "2") (pinfunction "B_2") (pintype "unspecified"))
      (node (ref "U2") (pin "7") (pinfunction "A5_7") (pintype "input"))
    )
    (net (code "11") (name "A6") (class "Default")
      (node (ref "RP1") (pin "8") (pintype "unspecified"))
      (node (ref "S1") (pin "10") (pinfunction "A6_10") (pintype "unspecified"))
      (node (ref "S2") (pin "10") (pinfunction "A6_10") (pintype "unspecified"))
      (node (ref "S3") (pin "10") (pinfunction "A6_10") (pintype "unspecified"))
      (node (ref "U1") (pin "36") (pinfunction "A6_36") (pintype "unspecified"))
      (node (ref "U11") (pin "3") (pinfunction "C_3") (pintype "unspecified"))
      (node (ref "U12") (pin "3") (pinfunction "C_3") (pintype "unspecified"))
      (node (ref "U13") (pin "3") (pinfunction "C_3") (pintype "unspecified"))
      (node (ref "U2") (pin "6") (pinfunction "A6_6") (pintype "input"))
    )
    (net (code "12") (name "A7") (class "Default")
      (node (ref "RP1") (pin "9") (pintype "unspecified"))
      (node (ref "S1") (pin "9") (pinfunction "A7_9") (pintype "unspecified"))
      (node (ref "S2") (pin "9") (pinfunction "A7_9") (pintype "unspecified"))
      (node (ref "S3") (pin "9") (pinfunction "A7_9") (pintype "unspecified"))
      (node (ref "U1") (pin "37") (pinfunction "A7_37") (pintype "unspecified"))
      (node (ref "U11") (pin "5") (pinfunction "G2B#_5") (pintype "unspecified"))
      (node (ref "U12") (pin "5") (pinfunction "G2B#_5") (pintype "unspecified"))
      (node (ref "U13") (pin "5") (pinfunction "G2B#_5") (pintype "unspecified"))
      (node (ref "U2") (pin "5") (pinfunction "A7_5") (pintype "input"))
    )
    (net (code "13") (name "A8") (class "Default")
      (node (ref "RP2") (pin "2") (pintype "unspecified"))
      (node (ref "S1") (pin "8") (pinfunction "A8_8") (pintype "unspecified"))
      (node (ref "S2") (pin "8") (pinfunction "A8_8") (pintype "unspecified"))
      (node (ref "S3") (pin "8") (pinfunction "A8_8") (pintype "unspecified"))
      (node (ref "U1") (pin "38") (pinfunction "A8_38") (pintype "unspecified"))
      (node (ref "U2") (pin "27") (pinfunction "A8_27") (pintype "input"))
    )
    (net (code "14") (name "A9") (class "Default")
      (node (ref "RP2") (pin "3") (pintype "unspecified"))
      (node (ref "S1") (pin "7") (pinfunction "A9_7") (pintype "unspecified"))
      (node (ref "S2") (pin "7") (pinfunction "A9_7") (pintype "unspecified"))
      (node (ref "S3") (pin "7") (pinfunction "A9_7") (pintype "unspecified"))
      (node (ref "U1") (pin "39") (pinfunction "A9_39") (pintype "unspecified"))
      (node (ref "U2") (pin "26") (pinfunction "A9_26") (pintype "input"))
    )
    (net (code "15") (name "A10") (class "Default")
      (node (ref "RP2") (pin "4") (pintype "unspecified"))
      (node (ref "S1") (pin "6") (pinfunction "A10_6") (pintype "unspecified"))
      (node (ref "S2") (pin "6") (pinfunction "A10_6") (pintype "unspecified"))
      (node (ref "S3") (pin "6") (pinfunction "A10_6") (pintype "unspecified"))
      (node (ref "U1") (pin "40") (pinfunction "A10_40") (pintype "unspecified"))
      (node (ref "U2") (pin "23") (pinfunction "A10_23") (pintype "input"))
    )
    (net (code "16") (name "A11") (class "Default")
      (node (ref "RP2") (pin "5") (pintype "unspecified"))
      (node (ref "S1") (pin "5") (pinfunction "A11_5") (pintype "unspecified"))
      (node (ref "S2") (pin "5") (pinfunction "A11_5") (pintype "unspecified"))
      (node (ref "S3") (pin "5") (pinfunction "A11_5") (pintype "unspecified"))
      (node (ref "U1") (pin "1") (pinfunction "A11_1") (pintype "unspecified"))
      (node (ref "U2") (pin "25") (pinfunction "A11_25") (pintype "input"))
    )
    (net (code "17") (name "A12") (class "Default")
      (node (ref "RP2") (pin "6") (pintype "unspecified"))
      (node (ref "S1") (pin "4") (pinfunction "A12_4") (pintype "unspecified"))
      (node (ref "S2") (pin "4") (pinfunction "A12_4") (pintype "unspecified"))
      (node (ref "S3") (pin "4") (pinfunction "A12_4") (pintype "unspecified"))
      (node (ref "U1") (pin "2") (pinfunction "A12_2") (pintype "unspecified"))
      (node (ref "U2") (pin "4") (pinfunction "A12_4") (pintype "input"))
    )
    (net (code "18") (name "A13") (class "Default")
      (node (ref "RP2") (pin "7") (pintype "unspecified"))
      (node (ref "S1") (pin "3") (pinfunction "A13_3") (pintype "unspecified"))
      (node (ref "S2") (pin "3") (pinfunction "A13_3") (pintype "unspecified"))
      (node (ref "S3") (pin "3") (pinfunction "A13_3") (pintype "unspecified"))
      (node (ref "U1") (pin "3") (pinfunction "A13_3") (pintype "unspecified"))
      (node (ref "U2") (pin "28") (pinfunction "A13_28") (pintype "input"))
    )
    (net (code "19") (name "A14") (class "Default")
      (node (ref "RP2") (pin "8") (pintype "unspecified"))
      (node (ref "S1") (pin "2") (pinfunction "A14_2") (pintype "unspecified"))
      (node (ref "S2") (pin "2") (pinfunction "A14_2") (pintype "unspecified"))
      (node (ref "S3") (pin "2") (pinfunction "A14_2") (pintype "unspecified"))
      (node (ref "U1") (pin "4") (pinfunction "A14_4") (pintype "unspecified"))
      (node (ref "U2") (pin "3") (pinfunction "A14_3") (pintype "input"))
    )
    (net (code "20") (name "A15") (class "Default")
      (node (ref "RP2") (pin "9") (pintype "unspecified"))
      (node (ref "S1") (pin "1") (pinfunction "A15_1") (pintype "unspecified"))
      (node (ref "S2") (pin "1") (pinfunction "A15_1") (pintype "unspecified"))
      (node (ref "S3") (pin "1") (pinfunction "A15_1") (pintype "unspecified"))
      (node (ref "U1") (pin "5") (pinfunction "A15_5") (pintype "unspecified"))
      (node (ref "U3") (pin "4") (pinfunction "2A_4") (pintype "unspecified"))
      (node (ref "U3") (pin "5") (pinfunction "2B_5") (pintype "unspecified"))
    )
    (net (code "21") (name "AUDIO_OUT") (class "Default")
      (node (ref "M1") (pin "23") (pinfunction "25-A1-D1_23") (pintype "unspecified"))
      (node (ref "R36") (pin "1") (pinfunction "1_1") (pintype "unspecified"))
    )
    (net (code "22") (name "B0") (class "Default")
      (node (ref "M1") (pin "5") (pinfunction "A5-4_5") (pintype "unspecified"))
      (node (ref "R19") (pin "2") (pinfunction "2_2") (pintype "unspecified"))
    )
    (net (code "23") (name "B1") (class "Default")
      (node (ref "M1") (pin "8") (pinfunction "SCK-5_8") (pintype "unspecified"))
      (node (ref "R18") (pin "2") (pinfunction "2_2") (pintype "unspecified"))
    )
    (net (code "24") (name "CEN1") (class "Default")
      (node (ref "S1") (pin "61") (pinfunction "CLK2_61") (pintype "unspecified"))
      (node (ref "U8") (pin "24") (pinfunction "GPA3_24") (pintype "unspecified"))
    )
    (net (code "25") (name "CEN2") (class "Default")
      (node (ref "S2") (pin "61") (pinfunction "CLK2_61") (pintype "unspecified"))
      (node (ref "U8") (pin "25") (pinfunction "GPA4_25") (pintype "unspecified"))
    )
    (net (code "26") (name "CEN3") (class "Default")
      (node (ref "S3") (pin "61") (pinfunction "CLK2_61") (pintype "unspecified"))
      (node (ref "U8") (pin "26") (pinfunction "GPA5_26") (pintype "unspecified"))
    )
    (net (code "27") (name "CLK") (class "Default")
      (node (ref "R58") (pin "1") (pinfunction "1_1") (pintype "unspecified"))
      (node (ref "S1") (pin "21") (pinfunction "CLK_21") (pintype "unspecified"))
      (node (ref "S2") (pin "21") (pinfunction "CLK_21") (pintype "unspecified"))
      (node (ref "S3") (pin "21") (pinfunction "CLK_21") (pintype "unspecified"))
      (node (ref "U1") (pin "6") (pinfunction "CLK_6") (pintype "unspecified"))
    )
    (net (code "28") (name "CPRES1") (class "Default")
      (node (ref "S1") (pin "60") (pinfunction "PAGE_60") (pintype "unspecified"))
      (node (ref "U8") (pin "21") (pinfunction "GPA0_21") (pintype "unspecified"))
    )
    (net (code "29") (name "CPRES2") (class "Default")
      (node (ref "S2") (pin "60") (pinfunction "PAGE_60") (pintype "unspecified"))
      (node (ref "U8") (pin "22") (pinfunction "GPA1_22") (pintype "unspecified"))
    )
    (net (code "30") (name "CPRES3") (class "Default")
      (node (ref "S3") (pin "60") (pinfunction "PAGE_60") (pintype "unspecified"))
      (node (ref "U8") (pin "23") (pinfunction "GPA2_23") (pintype "unspecified"))
    )
    (net (code "31") (name "D0") (class "Default")
      (node (ref "S1") (pin "27") (pinfunction "D0_27") (pintype "unspecified"))
      (node (ref "S2") (pin "27") (pinfunction "D0_27") (pintype "unspecified"))
      (node (ref "S3") (pin "27") (pinfunction "D0_27") (pintype "unspecified"))
      (node (ref "U1") (pin "14") (pinfunction "D0_14") (pintype "unspecified"))
      (node (ref "U2") (pin "12") (pinfunction "IO1_12") (pintype "bidirectional"))
      (node (ref "U4") (pin "40") (pinfunction "PA0_40") (pintype "unspecified"))
    )
    (net (code "32") (name "D1") (class "Default")
      (node (ref "S1") (pin "28") (pinfunction "D1_28") (pintype "unspecified"))
      (node (ref "S2") (pin "28") (pinfunction "D1_28") (pintype "unspecified"))
      (node (ref "S3") (pin "28") (pinfunction "D1_28") (pintype "unspecified"))
      (node (ref "U1") (pin "15") (pinfunction "D1_15") (pintype "unspecified"))
      (node (ref "U2") (pin "13") (pinfunction "IO2_13") (pintype "bidirectional"))
      (node (ref "U4") (pin "39") (pinfunction "PA1_39") (pintype "unspecified"))
    )
    (net (code "33") (name "D2") (class "Default")
      (node (ref "S1") (pin "29") (pinfunction "D2_29") (pintype "unspecified"))
      (node (ref "S2") (pin "29") (pinfunction "D2_29") (pintype "unspecified"))
      (node (ref "S3") (pin "29") (pinfunction "D2_29") (pintype "unspecified"))
      (node (ref "U1") (pin "12") (pinfunction "D2_12") (pintype "unspecified"))
      (node (ref "U2") (pin "14") (pinfunction "IO3_14") (pintype "bidirectional"))
      (node (ref "U4") (pin "38") (pinfunction "PA2_38") (pintype "unspecified"))
    )
    (net (code "34") (name "D3") (class "Default")
      (node (ref "S1") (pin "30") (pinfunction "D3_30") (pintype "unspecified"))
      (node (ref "S2") (pin "30") (pinfunction "D3_30") (pintype "unspecified"))
      (node (ref "S3") (pin "30") (pinfunction "D3_30") (pintype "unspecified"))
      (node (ref "U1") (pin "8") (pinfunction "D3_8") (pintype "unspecified"))
      (node (ref "U2") (pin "17") (pinfunction "IO4_17") (pintype "bidirectional"))
      (node (ref "U4") (pin "37") (pinfunction "PA3_37") (pintype "unspecified"))
    )
    (net (code "35") (name "D4") (class "Default")
      (node (ref "S1") (pin "31") (pinfunction "D4_31") (pintype "unspecified"))
      (node (ref "S2") (pin "31") (pinfunction "D4_31") (pintype "unspecified"))
      (node (ref "S3") (pin "31") (pinfunction "D4_31") (pintype "unspecified"))
      (node (ref "U1") (pin "7") (pinfunction "D4_7") (pintype "unspecified"))
      (node (ref "U2") (pin "18") (pinfunction "IO5_18") (pintype "bidirectional"))
      (node (ref "U4") (pin "36") (pinfunction "PA4_36") (pintype "unspecified"))
    )
    (net (code "36") (name "D5") (class "Default")
      (node (ref "S1") (pin "32") (pinfunction "D5_32") (pintype "unspecified"))
      (node (ref "S2") (pin "32") (pinfunction "D5_32") (pintype "unspecified"))
      (node (ref "S3") (pin "32") (pinfunction "D5_32") (pintype "unspecified"))
      (node (ref "U1") (pin "9") (pinfunction "D5_9") (pintype "unspecified"))
      (node (ref "U2") (pin "19") (pinfunction "IO6_19") (pintype "bidirectional"))
      (node (ref "U4") (pin "35") (pinfunction "PA5_35") (pintype "unspecified"))
    )
    (net (code "37") (name "D6") (class "Default")
      (node (ref "S1") (pin "33") (pinfunction "D6_33") (pintype "unspecified"))
      (node (ref "S2") (pin "33") (pinfunction "D6_33") (pintype "unspecified"))
      (node (ref "S3") (pin "33") (pinfunction "D6_33") (pintype "unspecified"))
      (node (ref "U1") (pin "10") (pinfunction "D6_10") (pintype "unspecified"))
      (node (ref "U2") (pin "20") (pinfunction "IO7_20") (pintype "bidirectional"))
      (node (ref "U4") (pin "34") (pinfunction "PA6_34") (pintype "unspecified"))
    )
    (net (code "38") (name "D7") (class "Default")
      (node (ref "S1") (pin "34") (pinfunction "D7_34") (pintype "unspecified"))
      (node (ref "S2") (pin "34") (pinfunction "D7_34") (pintype "unspecified"))
      (node (ref "S3") (pin "34") (pinfunction "D7_34") (pintype "unspecified"))
      (node (ref "U1") (pin "13") (pinfunction "D7_13") (pintype "unspecified"))
      (node (ref "U2") (pin "21") (pinfunction "IO8_21") (pintype "bidirectional"))
      (node (ref "U4") (pin "33") (pinfunction "PA7_33") (pintype "unspecified"))
    )
    (net (code "39") (name "D8") (class "Default")
      (node (ref "S1") (pin "67") (pinfunction "D8_67") (pintype "unspecified"))
      (node (ref "S2") (pin "67") (pinfunction "D8_67") (pintype "unspecified"))
      (node (ref "S3") (pin "67") (pinfunction "D8_67") (pintype "unspecified"))
    )
    (net (code "40") (name "D9") (class "Default")
      (node (ref "S1") (pin "68") (pinfunction "D9_68") (pintype "unspecified"))
      (node (ref "S2") (pin "68") (pinfunction "D9_68") (pintype "unspecified"))
      (node (ref "S3") (pin "68") (pinfunction "D9_68") (pintype "unspecified"))
    )
    (net (code "41") (name "D10") (class "Default")
      (node (ref "S1") (pin "69") (pinfunction "D10_69") (pintype "unspecified"))
      (node (ref "S2") (pin "69") (pinfunction "D10_69") (pintype "unspecified"))
      (node (ref "S3") (pin "69") (pinfunction "D10_69") (pintype "unspecified"))
    )
    (net (code "42") (name "D11") (class "Default")
      (node (ref "S1") (pin "70") (pinfunction "D11_70") (pintype "unspecified"))
      (node (ref "S2") (pin "70") (pinfunction "D11_70") (pintype "unspecified"))
      (node (ref "S3") (pin "70") (pinfunction "D11_70") (pintype "unspecified"))
    )
    (net (code "43") (name "D12") (class "Default")
      (node (ref "S1") (pin "71") (pinfunction "D12_71") (pintype "unspecified"))
      (node (ref "S2") (pin "71") (pinfunction "D12_71") (pintype "unspecified"))
      (node (ref "S3") (pin "71") (pinfunction "D12_71") (pintype "unspecified"))
    )
    (net (code "44") (name "D13") (class "Default")
      (node (ref "S1") (pin "72") (pinfunction "D13_72") (pintype "unspecified"))
      (node (ref "S2") (pin "72") (pinfunction "D13_72") (pintype "unspecified"))
      (node (ref "S3") (pin "72") (pinfunction "D13_72") (pintype "unspecified"))
    )
    (net (code "45") (name "D14") (class "Default")
      (node (ref "S1") (pin "73") (pinfunction "D14_73") (pintype "unspecified"))
      (node (ref "S2") (pin "73") (pinfunction "D14_73") (pintype "unspecified"))
      (node (ref "S3") (pin "73") (pinfunction "D14_73") (pintype "unspecified"))
    )
    (net (code "46") (name "D15") (class "Default")
      (node (ref "S1") (pin "74") (pinfunction "D15_74") (pintype "unspecified"))
      (node (ref "S2") (pin "74") (pinfunction "D15_74") (pintype "unspecified"))
      (node (ref "S3") (pin "74") (pinfunction "D15_74") (pintype "unspecified"))
    )
    (net (code "47") (name "DTR") (class "Default")
      (node (ref "C15") (pin "1") (pinfunction "1_1") (pintype "unspecified"))
      (node (ref "P1") (pin "4") (pinfunction "4_4") (pintype "unspecified"))
    )
    (net (code "48") (name "G0") (class "Default")
      (node (ref "M1") (pin "9") (pinfunction "MOSI-18_9") (pintype "unspecified"))
      (node (ref "R21") (pin "2") (pinfunction "2_2") (pintype "unspecified"))
    )
    (net (code "49") (name "G1") (class "Default")
      (node (ref "M1") (pin "10") (pinfunction "MISO-19_10") (pintype "unspecified"))
      (node (ref "R20") (pin "2") (pinfunction "2_2") (pintype "unspecified"))
    )
    (net (code "50") (name "GND") (class "Default")
      (node (ref "C1") (pin "2") (pinfunction "2_2") (pintype "unspecified"))
      (node (ref "C11") (pin "2") (pinfunction "2_2") (pintype "unspecified"))
      (node (ref "C12") (pin "2") (pinfunction "2_2") (pintype "unspecified"))
      (node (ref "C13") (pin "2") (pinfunction "2_2") (pintype "unspecified"))
      (node (ref "C14") (pin "2") (pinfunction "2_2") (pintype "unspecified"))
      (node (ref "C16") (pin "2") (pinfunction "2_2") (pintype "unspecified"))
      (node (ref "C17") (pin "2") (pinfunction "2_2") (pintype "unspecified"))
      (node (ref "C18") (pin "1") (pinfunction "1_1") (pintype "unspecified"))
      (node (ref "C19") (pin "1") (pinfunction "1_1") (pintype "unspecified"))
      (node (ref "C2") (pin "2") (pinfunction "2_2") (pintype "unspecified"))
      (node (ref "C20") (pin "1") (pinfunction "1_1") (pintype "unspecified"))
      (node (ref "C21") (pin "2") (pinfunction "2_2") (pintype "unspecified"))
      (node (ref "C22") (pin "2") (pinfunction "2_2") (pintype "unspecified"))
      (node (ref "C23") (pin "2") (pinfunction "2_2") (pintype "unspecified"))
      (node (ref "C24") (pin "2") (pinfunction "2_2") (pintype "unspecified"))
      (node (ref "C25") (pin "2") (pinfunction "2_2") (pintype "unspecified"))
      (node (ref "C26") (pin "2") (pinfunction "2_2") (pintype "unspecified"))
      (node (ref "C27") (pin "2") (pinfunction "2_2") (pintype "unspecified"))
      (node (ref "C28") (pin "2") (pinfunction "2_2") (pintype "unspecified"))
      (node (ref "C3") (pin "2") (pinfunction "2_2") (pintype "unspecified"))
      (node (ref "C4") (pin "2") (pinfunction "2_2") (pintype "unspecified"))
      (node (ref "C5") (pin "1") (pinfunction "1_1") (pintype "unspecified"))
      (node (ref "C8") (pin "2") (pinfunction "2_2") (pintype "unspecified"))
      (node (ref "C9") (pin "2") (pinfunction "2_2") (pintype "unspecified"))
      (node (ref "CR2032") (pin "2") (pinfunction "2_2") (pintype "input"))
      (node (ref "H1") (pin "1") (pinfunction "1_1") (pintype "unspecified"))
      (node (ref "H2") (pin "1") (pinfunction "1_1") (pintype "unspecified"))
      (node (ref "H3") (pin "6") (pinfunction "GND_6") (pintype "unspecified"))
      (node (ref "H4") (pin "1") (pinfunction "1_1") (pintype "unspecified"))
      (node (ref "JP2") (pin "SLEEVE") (pinfunction "SLEEVE_SLEEVE") (pintype "unspecified"))
      (node (ref "JP5") (pin "1") (pinfunction "1_1") (pintype "unspecified"))
      (node (ref "JP7") (pin "1") (pinfunction "1_1") (pintype "unspecified"))
      (node (ref "JP8") (pin "1") (pinfunction "1_1") (pintype "unspecified"))
      (node (ref "KEYBOARD") (pin "3") (pinfunction "GND_3") (pintype "unspecified"))
      (node (ref "KEYBOARD") (pin "7") (pinfunction "7_7") (pintype "unspecified"))
      (node (ref "KEYBOARD") (pin "8") (pinfunction "8_8") (pintype "unspecified"))
      (node (ref "KEYBOARD") (pin "9") (pinfunction "9_9") (pintype "unspecified"))
      (node (ref "LED2") (pin "2") (pinfunction "K_2") (pintype "input"))
      (node (ref "LED3") (pin "2") (pinfunction "K_2") (pintype "input"))
      (node (ref "LED5") (pin "2") (pinfunction "K_2") (pintype "input"))
      (node (ref "LM386") (pin "2") (pinfunction "2_2") (pintype "input"))
      (node (ref "LM386") (pin "4") (pinfunction "4_4") (pintype "unspecified"))
      (node (ref "M1") (pin "30") (pinfunction "Gnd_30") (pintype "unspecified"))
      (node (ref "M1") (pin "36") (pinfunction "Gnd_36") (pintype "unspecified"))
      (node (ref "MOUSE") (pin "3") (pinfunction "GND_3") (pintype "unspecified"))
      (node (ref "MOUSE") (pin "7") (pinfunction "7_7") (pintype "unspecified"))
      (node (ref "MOUSE") (pin "8") (pinfunction "8_8") (pintype "unspecified"))
      (node (ref "MOUSE") (pin "9") (pinfunction "9_9") (pintype "unspecified"))
      (node (ref "P1") (pin "5") (pinfunction "5_5") (pintype "unspecified"))
      (node (ref "R2") (pin "2") (pinfunction "2_2") (pintype "unspecified"))
      (node (ref "R34") (pin "2") (pinfunction "2_2") (pintype "unspecified"))
      (node (ref "R35") (pin "2") (pinfunction "2_2") (pintype "unspecified"))
      (node (ref "R39") (pin "2") (pinfunction "2_2") (pintype "unspecified"))
      (node (ref "R46") (pin "2") (pinfunction "2_2") (pintype "unspecified"))
      (node (ref "R57") (pin "2") (pinfunction "2_2") (pintype "unspecified"))
      (node (ref "R8") (pin "2") (pinfunction "2_2") (pintype "unspecified"))
      (node (ref "S1") (pin "17") (pinfunction "GND_17") (pintype "unspecified"))
      (node (ref "S1") (pin "39") (pinfunction "USR3_39") (pintype "unspecified"))
      (node (ref "S1") (pin "57") (pinfunction "GND_57") (pintype "unspecified"))
      (node (ref "S1") (pin "79") (pinfunction "USR7_79") (pintype "unspecified"))
      (node (ref "S2") (pin "17") (pinfunction "GND_17") (pintype "unspecified"))
      (node (ref "S2") (pin "39") (pinfunction "USR3_39") (pintype "unspecified"))
      (node (ref "S2") (pin "57") (pinfunction "GND_57") (pintype "unspecified"))
      (node (ref "S2") (pin "79") (pinfunction "USR7_79") (pintype "unspecified"))
      (node (ref "S3") (pin "17") (pinfunction "GND_17") (pintype "unspecified"))
      (node (ref "S3") (pin "39") (pinfunction "USR3_39") (pintype "unspecified"))
      (node (ref "S3") (pin "57") (pinfunction "GND_57") (pintype "unspecified"))
      (node (ref "S3") (pin "79") (pinfunction "USR7_79") (pintype "unspecified"))
      (node (ref "SPK") (pin "2") (pinfunction "-_2") (pintype "unspecified"))
      (node (ref "SW1") (pin "1") (pinfunction "1_1") (pintype "unspecified"))
      (node (ref "SW1") (pin "2") (pinfunction "2_2") (pintype "unspecified"))
      (node (ref "SW2") (pin "3") (pinfunction "3_3") (pintype "unspecified"))
      (node (ref "SW2") (pin "4") (pinfunction "4_4") (pintype "unspecified"))
      (node (ref "U1") (pin "29") (pinfunction "GND_29") (pintype "unspecified"))
      (node (ref "U10") (pin "15") (pinfunction "15_15") (pintype "unspecified"))
      (node (ref "U10") (pin "17") (pinfunction "17_17") (pintype "unspecified"))
      (node (ref "U10") (pin "18") (pinfunction "18_18") (pintype "unspecified"))
      (node (ref "U10") (pin "19") (pinfunction "19_19") (pintype "unspecified"))
      (node (ref "U10") (pin "24") (pinfunction "24_24") (pintype "unspecified"))
      (node (ref "U10") (pin "3") (pinfunction "3_3") (pintype "unspecified"))
      (node (ref "U10") (pin "5") (pinfunction "5_5") (pintype "unspecified"))
      (node (ref "U11") (pin "8") (pinfunction "GND_8") (pintype "unspecified"))
      (node (ref "U12") (pin "8") (pinfunction "GND_8") (pintype "unspecified"))
      (node (ref "U13") (pin "8") (pinfunction "GND_8") (pintype "unspecified"))
      (node (ref "U2") (pin "16") (pinfunction "GND_16") (pintype "passive"))
      (node (ref "U3") (pin "7") (pinfunction "GND_7") (pintype "unspecified"))
      (node (ref "U4") (pin "11") (pinfunction "GND_11") (pintype "unspecified"))
      (node (ref "U4") (pin "31") (pinfunction "GND_31") (pintype "unspecified"))
      (node (ref "U5") (pin "4") (pinfunction "GND_4") (pintype "unspecified"))
      (node (ref "U6") (pin "1") (pinfunction "GND_1") (pintype "unspecified"))
      (node (ref "U7") (pin "10") (pinfunction "VSS_10") (pintype "unspecified"))
      (node (ref "U7") (pin "15") (pinfunction "A0_15") (pintype "unspecified"))
      (node (ref "U7") (pin "16") (pinfunction "A1_16") (pintype "unspecified"))
      (node (ref "U7") (pin "17") (pinfunction "A2_17") (pintype "unspecified"))
      (node (ref "U8") (pin "10") (pinfunction "VSS_10") (pintype "unspecified"))
      (node (ref "U8") (pin "15") (pinfunction "A0_15") (pintype "unspecified"))
      (node (ref "U8") (pin "17") (pinfunction "A2_17") (pintype "unspecified"))
      (node (ref "U9") (pin "1") (pinfunction "GND_1") (pintype "unspecified"))
      (node (ref "VGA") (pin "10") (pinfunction "10_10") (pintype "unspecified"))
      (node (ref "VGA") (pin "16") (pinfunction "16_16") (pintype "unspecified"))
      (node (ref "VGA") (pin "17") (pinfunction "17_17") (pintype "unspecified"))
      (node (ref "VGA") (pin "5") (pinfunction "5_5") (pintype "unspecified"))
      (node (ref "VGA") (pin "6") (pinfunction "6_6") (pintype "unspecified"))
      (node (ref "VGA") (pin "7") (pinfunction "7_7") (pintype "unspecified"))
      (node (ref "VGA") (pin "8") (pinfunction "8_8") (pintype "unspecified"))
    )
    (net (code "51") (name "GPA0") (class "Default")
      (node (ref "S1") (pin "48") (pinfunction "Pin48_48") (pintype "unspecified"))
      (node (ref "S2") (pin "48") (pinfunction "Pin48_48") (pintype "unspecified"))
      (node (ref "S3") (pin "48") (pinfunction "Pin48_48") (pintype "unspecified"))
      (node (ref "U7") (pin "21") (pinfunction "GPA0_21") (pintype "unspecified"))
    )
    (net (code "52") (name "GPA1") (class "Default")
      (node (ref "S1") (pin "47") (pinfunction "Pin47_47") (pintype "unspecified"))
      (node (ref "S2") (pin "47") (pinfunction "Pin47_47") (pintype "unspecified"))
      (node (ref "S3") (pin "47") (pinfunction "Pin47_47") (pintype "unspecified"))
      (node (ref "U7") (pin "22") (pinfunction "GPA1_22") (pintype "unspecified"))
    )
    (net (code "53") (name "GPA2") (class "Default")
      (node (ref "S1") (pin "46") (pinfunction "Pin46_46") (pintype "unspecified"))
      (node (ref "S2") (pin "46") (pinfunction "Pin46_46") (pintype "unspecified"))
      (node (ref "S3") (pin "46") (pinfunction "Pin46_46") (pintype "unspecified"))
      (node (ref "U7") (pin "23") (pinfunction "GPA2_23") (pintype "unspecified"))
    )
    (net (code "54") (name "GPA3") (class "Default")
      (node (ref "S1") (pin "45") (pinfunction "Pin45_45") (pintype "unspecified"))
      (node (ref "S2") (pin "45") (pinfunction "Pin45_45") (pintype "unspecified"))
      (node (ref "S3") (pin "45") (pinfunction "Pin45_45") (pintype "unspecified"))
      (node (ref "U7") (pin "24") (pinfunction "GPA3_24") (pintype "unspecified"))
    )
    (net (code "55") (name "GPA4") (class "Default")
      (node (ref "S1") (pin "44") (pinfunction "Pin44_44") (pintype "unspecified"))
      (node (ref "S2") (pin "44") (pinfunction "Pin44_44") (pintype "unspecified"))
      (node (ref "S3") (pin "44") (pinfunction "Pin44_44") (pintype "unspecified"))
      (node (ref "U7") (pin "25") (pinfunction "GPA4_25") (pintype "unspecified"))
    )
    (net (code "56") (name "GPA5") (class "Default")
      (node (ref "S1") (pin "43") (pinfunction "Pin43_43") (pintype "unspecified"))
      (node (ref "S2") (pin "43") (pinfunction "Pin43_43") (pintype "unspecified"))
      (node (ref "S3") (pin "43") (pinfunction "Pin43_43") (pintype "unspecified"))
      (node (ref "U7") (pin "26") (pinfunction "GPA5_26") (pintype "unspecified"))
    )
    (net (code "57") (name "GPA6") (class "Default")
      (node (ref "S1") (pin "42") (pinfunction "Pin42_42") (pintype "unspecified"))
      (node (ref "S2") (pin "42") (pinfunction "Pin42_42") (pintype "unspecified"))
      (node (ref "S3") (pin "42") (pinfunction "Pin42_42") (pintype "unspecified"))
      (node (ref "U7") (pin "27") (pinfunction "GPA6_27") (pintype "unspecified"))
    )
    (net (code "58") (name "GPA7") (class "Default")
      (node (ref "S1") (pin "41") (pinfunction "Pin41_41") (pintype "unspecified"))
      (node (ref "S2") (pin "41") (pinfunction "Pin41_41") (pintype "unspecified"))
      (node (ref "S3") (pin "41") (pinfunction "Pin41_41") (pintype "unspecified"))
      (node (ref "U7") (pin "28") (pinfunction "GPA7_28") (pintype "unspecified"))
    )
    (net (code "59") (name "GPB0") (class "Default")
      (node (ref "S1") (pin "49") (pinfunction "A23_49") (pintype "unspecified"))
      (node (ref "S2") (pin "49") (pinfunction "A23_49") (pintype "unspecified"))
      (node (ref "S3") (pin "49") (pinfunction "A23_49") (pintype "unspecified"))
      (node (ref "U7") (pin "1") (pinfunction "GPB0_1") (pintype "unspecified"))
    )
    (net (code "60") (name "GPB1") (class "Default")
      (node (ref "S1") (pin "50") (pinfunction "A22_50") (pintype "unspecified"))
      (node (ref "S2") (pin "50") (pinfunction "A22_50") (pintype "unspecified"))
      (node (ref "S3") (pin "50") (pinfunction "A22_50") (pintype "unspecified"))
      (node (ref "U7") (pin "2") (pinfunction "GPB1_2") (pintype "unspecified"))
    )
    (net (code "61") (name "GPB2") (class "Default")
      (node (ref "S1") (pin "51") (pinfunction "A21_51") (pintype "unspecified"))
      (node (ref "S2") (pin "51") (pinfunction "A21_51") (pintype "unspecified"))
      (node (ref "S3") (pin "51") (pinfunction "A21_51") (pintype "unspecified"))
      (node (ref "U7") (pin "3") (pinfunction "GPB2_3") (pintype "unspecified"))
    )
    (net (code "62") (name "GPB3") (class "Default")
      (node (ref "S1") (pin "52") (pinfunction "A20_52") (pintype "unspecified"))
      (node (ref "S2") (pin "52") (pinfunction "A20_52") (pintype "unspecified"))
      (node (ref "S3") (pin "52") (pinfunction "A20_52") (pintype "unspecified"))
      (node (ref "U7") (pin "4") (pinfunction "GPB3_4") (pintype "unspecified"))
    )
    (net (code "63") (name "GPB4") (class "Default")
      (node (ref "S1") (pin "53") (pinfunction "A19_53") (pintype "unspecified"))
      (node (ref "S2") (pin "53") (pinfunction "A19_53") (pintype "unspecified"))
      (node (ref "S3") (pin "53") (pinfunction "A19_53") (pintype "unspecified"))
      (node (ref "U7") (pin "5") (pinfunction "GPB4_5") (pintype "unspecified"))
    )
    (net (code "64") (name "GPB5") (class "Default")
      (node (ref "S1") (pin "54") (pinfunction "A18_54") (pintype "unspecified"))
      (node (ref "S2") (pin "54") (pinfunction "A18_54") (pintype "unspecified"))
      (node (ref "S3") (pin "54") (pinfunction "A18_54") (pintype "unspecified"))
      (node (ref "U7") (pin "6") (pinfunction "GPB5_6") (pintype "unspecified"))
    )
    (net (code "65") (name "GPB6") (class "Default")
      (node (ref "S1") (pin "55") (pinfunction "A17_55") (pintype "unspecified"))
      (node (ref "S2") (pin "55") (pinfunction "A17_55") (pintype "unspecified"))
      (node (ref "S3") (pin "55") (pinfunction "A17_55") (pintype "unspecified"))
      (node (ref "U7") (pin "7") (pinfunction "GPB6_7") (pintype "unspecified"))
    )
    (net (code "66") (name "GPB7") (class "Default")
      (node (ref "S1") (pin "56") (pinfunction "A16_56") (pintype "unspecified"))
      (node (ref "S2") (pin "56") (pinfunction "A16_56") (pintype "unspecified"))
      (node (ref "S3") (pin "56") (pinfunction "A16_56") (pintype "unspecified"))
      (node (ref "U7") (pin "8") (pinfunction "GPB7_8") (pintype "unspecified"))
    )
    (net (code "67") (name "HSYNC") (class "Default")
      (node (ref "M1") (pin "15") (pinfunction "SDA-23_15") (pintype "unspecified"))
      (node (ref "R17") (pin "2") (pinfunction "2_2") (pintype "unspecified"))
    )
    (net (code "68") (name "I_CAS1") (class "Default")
      (node (ref "S1") (pin "80") (pinfunction "IEI_80") (pintype "unspecified"))
      (node (ref "S2") (pin "40") (pinfunction "IEO_40") (pintype "unspecified"))
    )
    (net (code "69") (name "I_CAS2") (class "Default")
      (node (ref "S2") (pin "80") (pinfunction "IEI_80") (pintype "unspecified"))
      (node (ref "S3") (pin "40") (pinfunction "IEO_40") (pintype "unspecified"))
    )
    (net (code "70") (name "MISO") (class "Default")
      (node (ref "H2") (pin "3") (pinfunction "3_3") (pintype "unspecified"))
      (node (ref "H3") (pin "1") (pinfunction "MISO_1") (pintype "unspecified"))
      (node (ref "R37") (pin "2") (pinfunction "2_2") (pintype "unspecified"))
      (node (ref "U4") (pin "7") (pinfunction "PB6_7") (pintype "unspecified"))
    )
    (net (code "71") (name "MOSI") (class "Default")
      (node (ref "H2") (pin "4") (pinfunction "4_4") (pintype "unspecified"))
      (node (ref "H3") (pin "4") (pinfunction "MOSI_4") (pintype "unspecified"))
      (node (ref "U4") (pin "6") (pinfunction "PB5_6") (pintype "unspecified"))
    )
    (net (code "72") (name "Net-(C6-Pad2)") (class "Default")
      (node (ref "C6") (pin "2") (pinfunction "2_2") (pintype "input"))
      (node (ref "LM386") (pin "3") (pinfunction "3_3") (pintype "input"))
      (node (ref "R34") (pin "1") (pinfunction "1_1") (pintype "unspecified"))
    )
    (net (code "73") (name "Net-(C7-Pad1)") (class "Default")
      (node (ref "C7") (pin "1") (pinfunction "1_1") (pintype "input"))
      (node (ref "LM386") (pin "5") (pinfunction "5_5") (pintype "unspecified"))
      (node (ref "R32") (pin "1") (pinfunction "1_1") (pintype "unspecified"))
      (node (ref "R33") (pin "2") (pinfunction "2_2") (pintype "unspecified"))
    )
    (net (code "74") (name "Net-(C9-Pad1)") (class "Default")
      (node (ref "C9") (pin "1") (pinfunction "1_1") (pintype "unspecified"))
      (node (ref "R32") (pin "2") (pinfunction "2_2") (pintype "unspecified"))
    )
    (net (code "75") (name "Net-(C10-Pad1)") (class "Default")
      (node (ref "C10") (pin "1") (pinfunction "1_1") (pintype "unspecified"))
      (node (ref "LM386") (pin "1") (pinfunction "1_1") (pintype "output"))
    )
    (net (code "76") (name "Net-(C10-Pad2)") (class "Default")
      (node (ref "C10") (pin "2") (pinfunction "2_2") (pintype "unspecified"))
      (node (ref "R33") (pin "1") (pinfunction "1_1") (pintype "unspecified"))
    )
    (net (code "77") (name "Net-(C11-Pad1)") (class "Default")
      (node (ref "C11") (pin "1") (pinfunction "1_1") (pintype "unspecified"))
      (node (ref "LM386") (pin "7") (pinfunction "7_7") (pintype "unspecified"))
    )
    (net (code "78") (name "Net-(C12-Pad1)") (class "Default")
      (node (ref "C12") (pin "1") (pinfunction "1_1") (pintype "unspecified"))
      (node (ref "C6") (pin "1") (pinfunction "1_1") (pintype "input"))
      (node (ref "R35") (pin "1") (pinfunction "1_1") (pintype "unspecified"))
      (node (ref "R36") (pin "2") (pinfunction "2_2") (pintype "unspecified"))
    )
    (net (code "79") (name "Net-(D3-K)") (class "Default")
      (node (ref "D3") (pin "1") (pinfunction "K_1") (pintype "unspecified"))
      (node (ref "JP10") (pin "1") (pinfunction "1_1") (pintype "unspecified"))
      (node (ref "LED4") (pin "1") (pinfunction "A_1") (pintype "input"))
    )
    (net (code "80") (name "Net-(D4-A)") (class "Default")
      (node (ref "D4") (pin "2") (pinfunction "A_2") (pintype "unspecified"))
      (node (ref "JP9") (pin "2") (pinfunction "2_2") (pintype "unspecified"))
      (node (ref "LED6") (pin "2") (pinfunction "K_2") (pintype "input"))
    )
    (net (code "81") (name "Net-(D4-K)") (class "Default")
      (node (ref "D4") (pin "1") (pinfunction "K_1") (pintype "unspecified"))
      (node (ref "R50") (pin "1") (pinfunction "1_1") (pintype "unspecified"))
    )
    (net (code "82") (name "Net-(H1-Pad4)") (class "Default")
      (node (ref "H1") (pin "4") (pinfunction "4_4") (pintype "unspecified"))
      (node (ref "M1") (pin "33") (pinfunction "RX_33") (pintype "unspecified"))
    )
    (net (code "83") (name "Net-(H1-Pad5)") (class "Default")
      (node (ref "H1") (pin "5") (pinfunction "5_5") (pintype "unspecified"))
      (node (ref "M1") (pin "32") (pinfunction "TX_32") (pintype "unspecified"))
    )
    (net (code "84") (name "Net-(H1-Pad6)") (class "Default")
      (node (ref "H1") (pin "6") (pinfunction "6_6") (pintype "unspecified"))
      (node (ref "M1") (pin "31") (pinfunction "31_31") (pintype "unspecified"))
    )
    (net (code "85") (name "Net-(JP2-LEFT)") (class "Default")
      (node (ref "C7") (pin "2") (pinfunction "2_2") (pintype "input"))
      (node (ref "JP2") (pin "RING") (pinfunction "RIGHT_RING") (pintype "unspecified"))
      (node (ref "JP2") (pin "TIP") (pinfunction "LEFT_TIP") (pintype "unspecified"))
    )
    (net (code "86") (name "Net-(JP7-Pad2)") (class "Default")
      (node (ref "JP7") (pin "2") (pinfunction "2_2") (pintype "unspecified"))
      (node (ref "R10") (pin "2") (pinfunction "2_2") (pintype "unspecified"))
      (node (ref "SW1") (pin "3") (pinfunction "3_3") (pintype "unspecified"))
      (node (ref "SW1") (pin "4") (pinfunction "4_4") (pintype "unspecified"))
    )
    (net (code "87") (name "Net-(KEYBOARD-CLK)") (class "Default")
      (node (ref "KEYBOARD") (pin "5") (pinfunction "CLK_5") (pintype "input"))
      (node (ref "R28") (pin "1") (pinfunction "1_1") (pintype "unspecified"))
      (node (ref "R30") (pin "1") (pinfunction "1_1") (pintype "unspecified"))
    )
    (net (code "88") (name "Net-(KEYBOARD-DATA)") (class "Default")
      (node (ref "KEYBOARD") (pin "1") (pinfunction "DATA_1") (pintype "bidirectional"))
      (node (ref "R29") (pin "1") (pinfunction "1_1") (pintype "unspecified"))
      (node (ref "R31") (pin "1") (pinfunction "1_1") (pintype "unspecified"))
    )
    (net (code "89") (name "Net-(LED1-A)") (class "Default")
      (node (ref "LED1") (pin "1") (pinfunction "A_1") (pintype "input"))
      (node (ref "U3") (pin "12") (pinfunction "4A_12") (pintype "unspecified"))
      (node (ref "U3") (pin "8") (pinfunction "3Y_8") (pintype "unspecified"))
    )
    (net (code "90") (name "Net-(LED1-K)") (class "Default")
      (node (ref "LED1") (pin "2") (pinfunction "K_2") (pintype "input"))
      (node (ref "R2") (pin "1") (pinfunction "1_1") (pintype "unspecified"))
    )
    (net (code "91") (name "Net-(LED2-A)") (class "Default")
      (node (ref "LED2") (pin "1") (pinfunction "A_1") (pintype "input"))
      (node (ref "R5") (pin "1") (pinfunction "1_1") (pintype "unspecified"))
    )
    (net (code "92") (name "Net-(LED3-A)") (class "Default")
      (node (ref "LED3") (pin "1") (pinfunction "A_1") (pintype "input"))
      (node (ref "R7") (pin "1") (pinfunction "1_1") (pintype "unspecified"))
    )
    (net (code "93") (name "Net-(LED4-K)") (class "Default")
      (node (ref "JP10") (pin "2") (pinfunction "2_2") (pintype "unspecified"))
      (node (ref "LED4") (pin "2") (pinfunction "K_2") (pintype "input"))
      (node (ref "R11") (pin "2") (pinfunction "2_2") (pintype "unspecified"))
    )
    (net (code "94") (name "Net-(LED5-A)") (class "Default")
      (node (ref "LED5") (pin "1") (pinfunction "A_1") (pintype "input"))
      (node (ref "R9") (pin "2") (pinfunction "2_2") (pintype "unspecified"))
    )
    (net (code "95") (name "Net-(LED7-Pad2)") (class "Default")
      (node (ref "LED7") (pin "2") (pinfunction "2_2") (pintype "unspecified"))
      (node (ref "R46") (pin "1") (pinfunction "1_1") (pintype "unspecified"))
    )
    (net (code "96") (name "Net-(M1-39-A3)") (class "Default")
      (node (ref "JP6") (pin "2") (pinfunction "2_2") (pintype "unspecified"))
      (node (ref "M1") (pin "18") (pinfunction "39-A3_18") (pintype "unspecified"))
      (node (ref "R57") (pin "1") (pinfunction "1_1") (pintype "unspecified"))
      (node (ref "SW3") (pin "3") (pinfunction "3_3") (pintype "unspecified"))
      (node (ref "SW3") (pin "4") (pinfunction "4_4") (pintype "unspecified"))
    )
    (net (code "97") (name "Net-(M1-45)") (class "Default")
      (node (ref "H1") (pin "2") (pinfunction "2_2") (pintype "unspecified"))
      (node (ref "H1") (pin "3") (pinfunction "3_3") (pintype "unspecified"))
      (node (ref "JP1") (pin "2") (pinfunction "2_2") (pintype "unspecified"))
      (node (ref "M1") (pin "34") (pinfunction "V+_34") (pintype "unspecified"))
      (node (ref "M1") (pin "35") (pinfunction "45_35") (pintype "unspecified"))
    )
    (net (code "98") (name "Net-(MOUSE-CLK)") (class "Default")
      (node (ref "MOUSE") (pin "5") (pinfunction "CLK_5") (pintype "input"))
      (node (ref "R24") (pin "1") (pinfunction "1_1") (pintype "unspecified"))
      (node (ref "R26") (pin "1") (pinfunction "1_1") (pintype "unspecified"))
    )
    (net (code "99") (name "Net-(MOUSE-DATA)") (class "Default")
      (node (ref "MOUSE") (pin "1") (pinfunction "DATA_1") (pintype "bidirectional"))
      (node (ref "R25") (pin "1") (pinfunction "1_1") (pintype "unspecified"))
      (node (ref "R27") (pin "1") (pinfunction "1_1") (pintype "unspecified"))
    )
    (net (code "100") (name "Net-(Q1-B)") (class "Default")
      (node (ref "Q1") (pin "2") (pinfunction "B_2") (pintype "unspecified"))
      (node (ref "R4") (pin "2") (pinfunction "2_2") (pintype "unspecified"))
    )
    (net (code "101") (name "Net-(Q1-C)") (class "Default")
      (node (ref "Q1") (pin "3") (pinfunction "C_3") (pintype "unspecified"))
      (node (ref "R5") (pin "2") (pinfunction "2_2") (pintype "unspecified"))
    )
    (net (code "102") (name "Net-(Q2-B)") (class "Default")
      (node (ref "Q2") (pin "2") (pinfunction "B_2") (pintype "unspecified"))
      (node (ref "R6") (pin "2") (pinfunction "2_2") (pintype "unspecified"))
    )
    (net (code "103") (name "Net-(Q2-C)") (class "Default")
      (node (ref "Q2") (pin "3") (pinfunction "C_3") (pintype "unspecified"))
      (node (ref "R7") (pin "2") (pinfunction "2_2") (pintype "unspecified"))
    )
    (net (code "104") (name "Net-(R16-Pad1)") (class "Default")
      (node (ref "R16") (pin "1") (pinfunction "1_1") (pintype "unspecified"))
      (node (ref "VGA") (pin "14") (pinfunction "14_14") (pintype "unspecified"))
    )
    (net (code "105") (name "Net-(R17-Pad1)") (class "Default")
      (node (ref "R17") (pin "1") (pinfunction "1_1") (pintype "unspecified"))
      (node (ref "VGA") (pin "13") (pinfunction "13_13") (pintype "unspecified"))
    )
    (net (code "106") (name "Net-(R18-Pad1)") (class "Default")
      (node (ref "R18") (pin "1") (pinfunction "1_1") (pintype "unspecified"))
      (node (ref "R19") (pin "1") (pinfunction "1_1") (pintype "unspecified"))
      (node (ref "VGA") (pin "3") (pinfunction "3_3") (pintype "unspecified"))
    )
    (net (code "107") (name "Net-(R20-Pad1)") (class "Default")
      (node (ref "R20") (pin "1") (pinfunction "1_1") (pintype "unspecified"))
      (node (ref "R21") (pin "1") (pinfunction "1_1") (pintype "unspecified"))
      (node (ref "VGA") (pin "2") (pinfunction "2_2") (pintype "unspecified"))
    )
    (net (code "108") (name "Net-(R22-Pad1)") (class "Default")
      (node (ref "R22") (pin "1") (pinfunction "1_1") (pintype "unspecified"))
      (node (ref "R23") (pin "1") (pinfunction "1_1") (pintype "unspecified"))
      (node (ref "VGA") (pin "1") (pinfunction "1_1") (pintype "unspecified"))
    )
    (net (code "109") (name "Net-(SPK-+)") (class "Default")
      (node (ref "SPK") (pin "1") (pinfunction "+_1") (pintype "unspecified"))
      (node (ref "U4") (pin "16") (pinfunction "PD2_16") (pintype "unspecified"))
    )
    (net (code "110") (name "Net-(U3-1A)") (class "Default")
      (node (ref "D2") (pin "1") (pinfunction "1_1") (pintype "unspecified"))
      (node (ref "U3") (pin "1") (pinfunction "1A_1") (pintype "unspecified"))
      (node (ref "U3") (pin "6") (pinfunction "2Y_6") (pintype "unspecified"))
    )
    (net (code "111") (name "Net-(U4-PD7)") (class "Default")
      (node (ref "R58") (pin "2") (pinfunction "2_2") (pintype "unspecified"))
      (node (ref "U4") (pin "21") (pinfunction "PD7_21") (pintype "unspecified"))
    )
    (net (code "112") (name "Net-(U4-XTAL1)") (class "Default")
      (node (ref "C5") (pin "2") (pinfunction "2_2") (pintype "unspecified"))
      (node (ref "U4") (pin "13") (pinfunction "XTAL1_13") (pintype "unspecified"))
      (node (ref "X1") (pin "2") (pinfunction "OSC2_2") (pintype "input"))
    )
    (net (code "113") (name "Net-(U4-XTAL2)") (class "Default")
      (node (ref "C4") (pin "1") (pinfunction "1_1") (pintype "unspecified"))
      (node (ref "U4") (pin "12") (pinfunction "XTAL2_12") (pintype "unspecified"))
      (node (ref "X1") (pin "1") (pinfunction "OSC1_1") (pintype "input"))
    )
    (net (code "114") (name "Net-(U5-VBAT)") (class "Default")
      (node (ref "CR2032") (pin "1") (pinfunction "1_1") (pintype "input"))
      (node (ref "U5") (pin "3") (pinfunction "VBAT_3") (pintype "unspecified"))
    )
    (net (code "115") (name "Net-(U5-X1)") (class "Default")
      (node (ref "U5") (pin "1") (pinfunction "X1_1") (pintype "unspecified"))
      (node (ref "X2") (pin "2") (pinfunction "2_2") (pintype "unspecified"))
    )
    (net (code "116") (name "Net-(U5-X2)") (class "Default")
      (node (ref "U5") (pin "2") (pinfunction "X2_2") (pintype "unspecified"))
      (node (ref "X2") (pin "1") (pinfunction "1_1") (pintype "unspecified"))
    )
    (net (code "117") (name "Net-(U7-RESET#)") (class "Default")
      (node (ref "R49") (pin "1") (pinfunction "1_1") (pintype "unspecified"))
      (node (ref "U7") (pin "18") (pinfunction "RESET#_18") (pintype "unspecified"))
    )
    (net (code "118") (name "Net-(U8-RESET#)") (class "Default")
      (node (ref "R59") (pin "1") (pinfunction "1_1") (pintype "unspecified"))
      (node (ref "U8") (pin "18") (pinfunction "RESET#_18") (pintype "unspecified"))
    )
    (net (code "119") (name "PB0") (class "Default")
      (node (ref "R9") (pin "1") (pinfunction "1_1") (pintype "unspecified"))
      (node (ref "U3") (pin "13") (pinfunction "AB_13") (pintype "unspecified"))
      (node (ref "U4") (pin "1") (pinfunction "PB0_1") (pintype "unspecified"))
    )
    (net (code "120") (name "PB1") (class "Default")
      (node (ref "S1") (pin "22") (pinfunction "/INT_22") (pintype "unspecified"))
      (node (ref "S2") (pin "22") (pinfunction "/INT_22") (pintype "unspecified"))
      (node (ref "S3") (pin "22") (pinfunction "/INT_22") (pintype "unspecified"))
      (node (ref "U1") (pin "16") (pinfunction "/INT_16") (pintype "unspecified"))
      (node (ref "U4") (pin "2") (pinfunction "PB1_2") (pintype "unspecified"))
    )
    (net (code "121") (name "PB2") (class "Default")
      (node (ref "U2") (pin "30") (pinfunction "CE2_30") (pintype "input"))
      (node (ref "U4") (pin "3") (pinfunction "PB2_3") (pintype "unspecified"))
    )
    (net (code "122") (name "PB3") (class "Default")
      (node (ref "S1") (pin "65") (pinfunction "/WAIT_65") (pintype "unspecified"))
      (node (ref "S2") (pin "65") (pinfunction "/WAIT_65") (pintype "unspecified"))
      (node (ref "S3") (pin "65") (pinfunction "/WAIT_65") (pintype "unspecified"))
      (node (ref "U1") (pin "24") (pinfunction "/WAIT_24") (pintype "unspecified"))
      (node (ref "U3") (pin "10") (pinfunction "3B_10") (pintype "unspecified"))
      (node (ref "U3") (pin "11") (pinfunction "4Y_11") (pintype "unspecified"))
      (node (ref "U4") (pin "4") (pinfunction "PB3_4") (pintype "unspecified"))
    )
    (net (code "123") (name "PC3") (class "Default")
      (node (ref "U1") (pin "22") (pinfunction "/WR_22") (pintype "unspecified"))
      (node (ref "U13") (pin "4") (pinfunction "G2A#_4") (pintype "unspecified"))
      (node (ref "U2") (pin "29") (pinfunction "R/W_29") (pintype "input"))
      (node (ref "U4") (pin "25") (pinfunction "PC3_25") (pintype "unspecified"))
    )
    (net (code "124") (name "PC4") (class "Default")
      (node (ref "U1") (pin "21") (pinfunction "/RD_21") (pintype "unspecified"))
      (node (ref "U12") (pin "4") (pinfunction "G2A#_4") (pintype "unspecified"))
      (node (ref "U2") (pin "24") (pinfunction "OE_24") (pintype "input"))
      (node (ref "U4") (pin "26") (pinfunction "PC4_26") (pintype "unspecified"))
    )
    (net (code "125") (name "PC5") (class "Default")
      (node (ref "S1") (pin "23") (pinfunction "/MREQ_23") (pintype "unspecified"))
      (node (ref "S2") (pin "23") (pinfunction "/MREQ_23") (pintype "unspecified"))
      (node (ref "S3") (pin "23") (pinfunction "/MREQ_23") (pintype "unspecified"))
      (node (ref "U1") (pin "19") (pinfunction "/MREQ_19") (pintype "unspecified"))
      (node (ref "U2") (pin "22") (pinfunction "CE1_22") (pintype "input"))
      (node (ref "U4") (pin "27") (pinfunction "PC5_27") (pintype "unspecified"))
    )
    (net (code "126") (name "PC6") (class "Default")
      (node (ref "D7") (pin "A") (pinfunction "A_A") (pintype "unspecified"))
      (node (ref "R8") (pin "1") (pinfunction "1_1") (pintype "unspecified"))
      (node (ref "S1") (pin "20") (pinfunction "/RESET_20") (pintype "unspecified"))
      (node (ref "S2") (pin "20") (pinfunction "/RESET_20") (pintype "unspecified"))
      (node (ref "S3") (pin "20") (pinfunction "/RESET_20") (pintype "unspecified"))
      (node (ref "U1") (pin "26") (pinfunction "/RESET_26") (pintype "unspecified"))
      (node (ref "U4") (pin "28") (pinfunction "PC6_28") (pintype "unspecified"))
    )
    (net (code "127") (name "PD3") (class "Default")
      (node (ref "D1") (pin "1") (pinfunction "1_1") (pintype "unspecified"))
      (node (ref "U4") (pin "17") (pinfunction "PD3_17") (pintype "unspecified"))
    )
    (net (code "128") (name "PD4") (class "Default")
      (node (ref "U3") (pin "2") (pinfunction "1B_2") (pintype "unspecified"))
      (node (ref "U4") (pin "18") (pinfunction "PD4_18") (pintype "unspecified"))
    )
    (net (code "129") (name "PD6") (class "Default")
      (node (ref "S1") (pin "64") (pinfunction "/BUSRQ_64") (pintype "unspecified"))
      (node (ref "S2") (pin "64") (pinfunction "/BUSRQ_64") (pintype "unspecified"))
      (node (ref "S3") (pin "64") (pinfunction "/BUSRQ_64") (pintype "unspecified"))
      (node (ref "U1") (pin "25") (pinfunction "/BUSRQ_25") (pintype "unspecified"))
      (node (ref "U4") (pin "20") (pinfunction "PD6_20") (pintype "unspecified"))
    )
    (net (code "130") (name "PS2_P0_CLK") (class "Default")
      (node (ref "M1") (pin "22") (pinfunction "33-A9_22") (pintype "unspecified"))
      (node (ref "R30") (pin "2") (pinfunction "2_2") (pintype "unspecified"))
    )
    (net (code "131") (name "PS2_P0_DAT") (class "Default")
      (node (ref "M1") (pin "21") (pinfunction "32-A7_21") (pintype "unspecified"))
      (node (ref "R31") (pin "2") (pinfunction "2_2") (pintype "unspecified"))
    )
    (net (code "132") (name "PS2_P1_CLK") (class "Default")
      (node (ref "M1") (pin "24") (pinfunction "26-A0_24") (pintype "unspecified"))
      (node (ref "R26") (pin "2") (pinfunction "2_2") (pintype "unspecified"))
    )
    (net (code "133") (name "PS2_P1_DAT") (class "Default")
      (node (ref "M1") (pin "25") (pinfunction "27-A10_25") (pintype "unspecified"))
      (node (ref "R27") (pin "2") (pinfunction "2_2") (pintype "unspecified"))
    )
    (net (code "134") (name "PS_ON_3V3") (class "Default")
      (node (ref "M1") (pin "26") (pinfunction "14-A6_26") (pintype "unspecified"))
      (node (ref "Q6") (pin "1") (pinfunction "S_1") (pintype "unspecified"))
      (node (ref "R48") (pin "2") (pinfunction "2_2") (pintype "unspecified"))
    )
    (net (code "135") (name "PWR_OK") (class "Default")
      (node (ref "JP8") (pin "2") (pinfunction "2_2") (pintype "unspecified"))
      (node (ref "LED7") (pin "1") (pinfunction "1_1") (pintype "unspecified"))
      (node (ref "Q9") (pin "3") (pinfunction "D_3") (pintype "unspecified"))
      (node (ref "R55") (pin "2") (pinfunction "2_2") (pintype "unspecified"))
      (node (ref "U10") (pin "8") (pinfunction "8_8") (pintype "unspecified"))
    )
    (net (code "136") (name "PWR_OK_3V3") (class "Default")
      (node (ref "M1") (pin "17") (pinfunction "36-A4_17") (pintype "unspecified"))
      (node (ref "Q9") (pin "1") (pinfunction "S_1") (pintype "unspecified"))
      (node (ref "R56") (pin "2") (pinfunction "2_2") (pintype "unspecified"))
    )
    (net (code "137") (name "R0") (class "Default")
      (node (ref "M1") (pin "11") (pinfunction "21_11") (pintype "unspecified"))
      (node (ref "R23") (pin "2") (pinfunction "2_2") (pintype "unspecified"))
    )
    (net (code "138") (name "R1") (class "Default")
      (node (ref "M1") (pin "14") (pinfunction "SCL-22_14") (pintype "unspecified"))
      (node (ref "R22") (pin "2") (pinfunction "2_2") (pintype "unspecified"))
    )
    (net (code "139") (name "RAM_A15") (class "Default")
      (node (ref "U2") (pin "31") (pinfunction "A15_31") (pintype "input"))
      (node (ref "U3") (pin "3") (pinfunction "1Y_3") (pintype "unspecified"))
    )
    (net (code "140") (name "RAM_A16") (class "Default")
      (node (ref "D1") (pin "2") (pinfunction "2_2") (pintype "unspecified"))
      (node (ref "D2") (pin "2") (pinfunction "2_2") (pintype "unspecified"))
      (node (ref "R3") (pin "2") (pinfunction "2_2") (pintype "unspecified"))
      (node (ref "U2") (pin "2") (pinfunction "A16_2") (pintype "input"))
    )
    (net (code "141") (name "RUN") (class "Default")
      (node (ref "Q5") (pin "3") (pinfunction "D_3") (pintype "unspecified"))
      (node (ref "R44") (pin "2") (pinfunction "2_2") (pintype "unspecified"))
      (node (ref "U4") (pin "29") (pinfunction "PC7_29") (pintype "unspecified"))
    )
    (net (code "142") (name "RUN_3V3") (class "Default")
      (node (ref "M1") (pin "27") (pinfunction "12-A11_27") (pintype "unspecified"))
      (node (ref "Q5") (pin "1") (pinfunction "S_1") (pintype "unspecified"))
      (node (ref "R45") (pin "2") (pinfunction "2_2") (pintype "unspecified"))
    )
    (net (code "143") (name "RX") (class "Default")
      (node (ref "JP3") (pin "1") (pinfunction "1_1") (pintype "unspecified"))
      (node (ref "Q3") (pin "3") (pinfunction "D_3") (pintype "unspecified"))
      (node (ref "R12") (pin "2") (pinfunction "2_2") (pintype "unspecified"))
      (node (ref "S1") (pin "36") (pinfunction "RX_36") (pintype "unspecified"))
      (node (ref "S2") (pin "36") (pinfunction "RX_36") (pintype "unspecified"))
      (node (ref "S3") (pin "36") (pinfunction "RX_36") (pintype "unspecified"))
    )
    (net (code "144") (name "RX2") (class "Default")
      (node (ref "S1") (pin "76") (pinfunction "RX2_76") (pintype "unspecified"))
      (node (ref "S2") (pin "76") (pinfunction "RX2_76") (pintype "unspecified"))
      (node (ref "S3") (pin "76") (pinfunction "RX2_76") (pintype "unspecified"))
    )
    (net (code "145") (name "RXD") (class "Default")
      (node (ref "H4") (pin "4") (pinfunction "4_4") (pintype "unspecified"))
      (node (ref "JP3") (pin "2") (pinfunction "2_2") (pintype "unspecified"))
      (node (ref "P1") (pin "2") (pinfunction "2_2") (pintype "unspecified"))
      (node (ref "U4") (pin "15") (pinfunction "PD1_15") (pintype "unspecified"))
    )
    (net (code "146") (name "RX_3V3") (class "Default")
      (node (ref "M1") (pin "19") (pinfunction "34-A2_19") (pintype "unspecified"))
      (node (ref "Q3") (pin "1") (pinfunction "S_1") (pintype "unspecified"))
      (node (ref "R13") (pin "2") (pinfunction "2_2") (pintype "unspecified"))
    )
    (net (code "147") (name "SB_3V3") (class "Default")
      (node (ref "JP6") (pin "1") (pinfunction "1_1") (pintype "unspecified"))
      (node (ref "M1") (pin "29") (pinfunction "3V_29") (pintype "unspecified"))
      (node (ref "Q6") (pin "2") (pinfunction "G_2") (pintype "unspecified"))
      (node (ref "R48") (pin "1") (pinfunction "1_1") (pintype "unspecified"))
      (node (ref "SW3") (pin "1") (pinfunction "1_1") (pintype "unspecified"))
      (node (ref "SW3") (pin "2") (pinfunction "2_2") (pintype "unspecified"))
    )
    (net (code "148") (name "SCK") (class "Default")
      (node (ref "H2") (pin "5") (pinfunction "5_5") (pintype "unspecified"))
      (node (ref "H3") (pin "3") (pinfunction "SCK_3") (pintype "unspecified"))
      (node (ref "JP9") (pin "1") (pinfunction "1_1") (pintype "unspecified"))
      (node (ref "LED6") (pin "1") (pinfunction "A_1") (pintype "input"))
      (node (ref "R39") (pin "1") (pinfunction "1_1") (pintype "unspecified"))
      (node (ref "U4") (pin "8") (pinfunction "PB7_8") (pintype "unspecified"))
    )
    (net (code "149") (name "SCL") (class "Default")
      (node (ref "Q8") (pin "3") (pinfunction "D_3") (pintype "unspecified"))
      (node (ref "R43") (pin "1") (pinfunction "1_1") (pintype "unspecified"))
      (node (ref "R53") (pin "2") (pinfunction "2_2") (pintype "unspecified"))
      (node (ref "S1") (pin "38") (pinfunction "USR2_38") (pintype "unspecified"))
      (node (ref "S2") (pin "38") (pinfunction "USR2_38") (pintype "unspecified"))
      (node (ref "S3") (pin "38") (pinfunction "USR2_38") (pintype "unspecified"))
      (node (ref "U4") (pin "22") (pinfunction "PC0_22") (pintype "unspecified"))
      (node (ref "U5") (pin "6") (pinfunction "SCL_6") (pintype "unspecified"))
    )
    (net (code "150") (name "SCL_3V3") (class "Default")
      (node (ref "Q8") (pin "1") (pinfunction "S_1") (pintype "unspecified"))
      (node (ref "R54") (pin "2") (pinfunction "2_2") (pintype "unspecified"))
      (node (ref "U7") (pin "12") (pinfunction "SCK_12") (pintype "unspecified"))
      (node (ref "U8") (pin "12") (pinfunction "SCK_12") (pintype "unspecified"))
    )
    (net (code "151") (name "SDA") (class "Default")
      (node (ref "Q7") (pin "3") (pinfunction "D_3") (pintype "unspecified"))
      (node (ref "R42") (pin "1") (pinfunction "1_1") (pintype "unspecified"))
      (node (ref "R51") (pin "2") (pinfunction "2_2") (pintype "unspecified"))
      (node (ref "S1") (pin "37") (pinfunction "USR1_37") (pintype "unspecified"))
      (node (ref "S2") (pin "37") (pinfunction "USR1_37") (pintype "unspecified"))
      (node (ref "S3") (pin "37") (pinfunction "USR1_37") (pintype "unspecified"))
      (node (ref "U4") (pin "23") (pinfunction "PC1_23") (pintype "unspecified"))
      (node (ref "U5") (pin "5") (pinfunction "SDA_5") (pintype "unspecified"))
    )
    (net (code "152") (name "SDA_3V3") (class "Default")
      (node (ref "Q7") (pin "1") (pinfunction "S_1") (pintype "unspecified"))
      (node (ref "R52") (pin "2") (pinfunction "2_2") (pintype "unspecified"))
      (node (ref "U7") (pin "13") (pinfunction "SDA_13") (pintype "unspecified"))
      (node (ref "U8") (pin "13") (pinfunction "SDA_13") (pintype "unspecified"))
    )
    (net (code "153") (name "SS") (class "Default")
      (node (ref "H2") (pin "6") (pinfunction "6_6") (pintype "unspecified"))
      (node (ref "R38") (pin "2") (pinfunction "2_2") (pintype "unspecified"))
      (node (ref "R50") (pin "2") (pinfunction "2_2") (pintype "unspecified"))
      (node (ref "U4") (pin "5") (pinfunction "PB4_5") (pintype "unspecified"))
    )
    (net (code "154") (name "SYS_RESET") (class "Default")
      (node (ref "C15") (pin "2") (pinfunction "2_2") (pintype "unspecified"))
      (node (ref "D5") (pin "2") (pinfunction "2_2") (pintype "unspecified"))
      (node (ref "H3") (pin "5") (pinfunction "RST_5") (pintype "unspecified"))
      (node (ref "R40") (pin "2") (pinfunction "2_2") (pintype "unspecified"))
      (node (ref "R41") (pin "2") (pinfunction "2_2") (pintype "unspecified"))
      (node (ref "U4") (pin "9") (pinfunction "RESET_9") (pintype "unspecified"))
    )
    (net (code "155") (name "TX") (class "Default")
      (node (ref "JP4") (pin "1") (pinfunction "1_1") (pintype "unspecified"))
      (node (ref "Q4") (pin "3") (pinfunction "D_3") (pintype "unspecified"))
      (node (ref "R14") (pin "2") (pinfunction "2_2") (pintype "unspecified"))
      (node (ref "S1") (pin "35") (pinfunction "TX_35") (pintype "unspecified"))
      (node (ref "S2") (pin "35") (pinfunction "TX_35") (pintype "unspecified"))
      (node (ref "S3") (pin "35") (pinfunction "TX_35") (pintype "unspecified"))
    )
    (net (code "156") (name "TX2") (class "Default")
      (node (ref "S1") (pin "75") (pinfunction "TX2_75") (pintype "unspecified"))
      (node (ref "S2") (pin "75") (pinfunction "TX2_75") (pintype "unspecified"))
      (node (ref "S3") (pin "75") (pinfunction "TX2_75") (pintype "unspecified"))
    )
    (net (code "157") (name "TXD") (class "Default")
      (node (ref "H4") (pin "5") (pinfunction "5_5") (pintype "unspecified"))
      (node (ref "JP4") (pin "2") (pinfunction "2_2") (pintype "unspecified"))
      (node (ref "P1") (pin "3") (pinfunction "3_3") (pintype "unspecified"))
      (node (ref "U4") (pin "14") (pinfunction "PD0_14") (pintype "unspecified"))
    )
    (net (code "158") (name "TX_3V3") (class "Default")
      (node (ref "M1") (pin "3") (pinfunction "2_3") (pintype "unspecified"))
      (node (ref "Q4") (pin "1") (pinfunction "S_1") (pintype "unspecified"))
      (node (ref "R15") (pin "1") (pinfunction "1_1") (pintype "unspecified"))
    )
    (net (code "159") (name "USER") (class "Default")
      (node (ref "R10") (pin "1") (pinfunction "1_1") (pintype "unspecified"))
      (node (ref "R11") (pin "1") (pinfunction "1_1") (pintype "unspecified"))
      (node (ref "U4") (pin "19") (pinfunction "PD5_19") (pintype "unspecified"))
    )
    (net (code "160") (name "VSYNC") (class "Default")
      (node (ref "M1") (pin "2") (pinfunction "A8-15_2") (pintype "unspecified"))
      (node (ref "R16") (pin "2") (pinfunction "2_2") (pintype "unspecified"))
    )
    (net (code "161") (name "unconnected-(H4-Pad2)") (class "Default")
      (node (ref "H4") (pin "2") (pinfunction "2_2") (pintype "unspecified+no_connect"))
    )
    (net (code "162") (name "unconnected-(H4-Pad6)") (class "Default")
      (node (ref "H4") (pin "6") (pinfunction "6_6") (pintype "unspecified+no_connect"))
    )
    (net (code "163") (name "unconnected-(KEYBOARD-NC-Pad2)") (class "Default")
      (node (ref "KEYBOARD") (pin "2") (pinfunction "NC_2") (pintype "unspecified+no_connect"))
    )
    (net (code "164") (name "unconnected-(KEYBOARD-NC-Pad6)") (class "Default")
      (node (ref "KEYBOARD") (pin "6") (pinfunction "NC_6") (pintype "unspecified+no_connect"))
    )
    (net (code "165") (name "unconnected-(LM386-Pad8)") (class "Default")
      (node (ref "LM386") (pin "8") (pinfunction "8_8") (pintype "passive+no_connect"))
    )
    (net (code "166") (name "unconnected-(M1-0-Pad4)") (class "Default")
      (node (ref "M1") (pin "4") (pinfunction "0_4") (pintype "unspecified+no_connect"))
    )
    (net (code "167") (name "unconnected-(M1-13-A12-Pad28)") (class "Default")
      (node (ref "M1") (pin "28") (pinfunction "13-A12_28") (pintype "unspecified+no_connect"))
    )
    (net (code "168") (name "unconnected-(M1-35-A13-Pad20)") (class "Default")
      (node (ref "M1") (pin "20") (pinfunction "35-A13_20") (pintype "unspecified+no_connect"))
    )
    (net (code "169") (name "unconnected-(M1-Bat-Pad1)") (class "Default")
      (node (ref "M1") (pin "1") (pinfunction "Bat_1") (pintype "unspecified+no_connect"))
    )
    (net (code "170") (name "unconnected-(M1-RX-Pad12)") (class "Default")
      (node (ref "M1") (pin "12") (pinfunction "RX_12") (pintype "unspecified+no_connect"))
    )
    (net (code "171") (name "unconnected-(M1-S1RX-16-Pad6)") (class "Default")
      (node (ref "M1") (pin "6") (pinfunction "S1RX-16_6") (pintype "unspecified+no_connect"))
    )
    (net (code "172") (name "unconnected-(M1-S1TX-17-Pad7)") (class "Default")
      (node (ref "M1") (pin "7") (pinfunction "S1TX-17_7") (pintype "unspecified+no_connect"))
    )
    (net (code "173") (name "unconnected-(M1-TX-Pad13)") (class "Default")
      (node (ref "M1") (pin "13") (pinfunction "TX_13") (pintype "unspecified+no_connect"))
    )
    (net (code "174") (name "unconnected-(MOUSE-NC-Pad2)") (class "Default")
      (node (ref "MOUSE") (pin "2") (pinfunction "NC_2") (pintype "unspecified+no_connect"))
    )
    (net (code "175") (name "unconnected-(MOUSE-NC-Pad6)") (class "Default")
      (node (ref "MOUSE") (pin "6") (pinfunction "NC_6") (pintype "unspecified+no_connect"))
    )
    (net (code "176") (name "unconnected-(P1-Pad1)") (class "Default")
      (node (ref "P1") (pin "1") (pinfunction "1_1") (pintype "unspecified+no_connect"))
    )
    (net (code "177") (name "unconnected-(P1-Pad6)") (class "Default")
      (node (ref "P1") (pin "6") (pinfunction "6_6") (pintype "unspecified+no_connect"))
    )
    (net (code "178") (name "unconnected-(P1-Pad7)") (class "Default")
      (node (ref "P1") (pin "7") (pinfunction "7_7") (pintype "unspecified+no_connect"))
    )
    (net (code "179") (name "unconnected-(P1-Pad8)") (class "Default")
      (node (ref "P1") (pin "8") (pinfunction "8_8") (pintype "unspecified+no_connect"))
    )
    (net (code "180") (name "unconnected-(P1-Pad9)") (class "Default")
      (node (ref "P1") (pin "9") (pinfunction "9_9") (pintype "unspecified+no_connect"))
    )
    (net (code "181") (name "unconnected-(S1-IEO-Pad40)") (class "Default")
      (node (ref "S1") (pin "40") (pinfunction "IEO_40") (pintype "unspecified+no_connect"))
    )
    (net (code "182") (name "unconnected-(S3-IEI-Pad80)") (class "Default")
      (node (ref "S3") (pin "80") (pinfunction "IEI_80") (pintype "unspecified+no_connect"))
    )
    (net (code "183") (name "unconnected-(U2-NC-Pad1)") (class "Default")
      (node (ref "U2") (pin "1") (pinfunction "NC_1") (pintype "unspecified+no_connect"))
    )
    (net (code "184") (name "unconnected-(U4-AREF-Pad32)") (class "Default")
      (node (ref "U4") (pin "32") (pinfunction "AREF_32") (pintype "unspecified+no_connect"))
    )
    (net (code "185") (name "unconnected-(U5-SQW{slash}OUT-Pad7)") (class "Default")
      (node (ref "U5") (pin "7") (pinfunction "SQW/OUT_7") (pintype "unspecified+no_connect"))
    )
    (net (code "186") (name "unconnected-(U7-INTA-Pad20)") (class "Default")
      (node (ref "U7") (pin "20") (pinfunction "INTA_20") (pintype "unspecified+no_connect"))
    )
    (net (code "187") (name "unconnected-(U7-INTB-Pad19)") (class "Default")
      (node (ref "U7") (pin "19") (pinfunction "INTB_19") (pintype "unspecified+no_connect"))
    )
    (net (code "188") (name "unconnected-(U7-NC-Pad11)") (class "Default")
      (node (ref "U7") (pin "11") (pinfunction "NC_11") (pintype "unspecified+no_connect"))
    )
    (net (code "189") (name "unconnected-(U7-NC-Pad14)") (class "Default")
      (node (ref "U7") (pin "14") (pinfunction "NC_14") (pintype "unspecified+no_connect"))
    )
    (net (code "190") (name "unconnected-(U8-GPA6-Pad27)") (class "Default")
      (node (ref "U8") (pin "27") (pinfunction "GPA6_27") (pintype "unspecified+no_connect"))
    )
    (net (code "191") (name "unconnected-(U8-GPA7-Pad28)") (class "Default")
      (node (ref "U8") (pin "28") (pinfunction "GPA7_28") (pintype "unspecified+no_connect"))
    )
    (net (code "192") (name "unconnected-(U8-GPB0-Pad1)") (class "Default")
      (node (ref "U8") (pin "1") (pinfunction "GPB0_1") (pintype "unspecified+no_connect"))
    )
    (net (code "193") (name "unconnected-(U8-GPB1-Pad2)") (class "Default")
      (node (ref "U8") (pin "2") (pinfunction "GPB1_2") (pintype "unspecified+no_connect"))
    )
    (net (code "194") (name "unconnected-(U8-GPB2-Pad3)") (class "Default")
      (node (ref "U8") (pin "3") (pinfunction "GPB2_3") (pintype "unspecified+no_connect"))
    )
    (net (code "195") (name "unconnected-(U8-GPB3-Pad4)") (class "Default")
      (node (ref "U8") (pin "4") (pinfunction "GPB3_4") (pintype "unspecified+no_connect"))
    )
    (net (code "196") (name "unconnected-(U8-GPB4-Pad5)") (class "Default")
      (node (ref "U8") (pin "5") (pinfunction "GPB4_5") (pintype "unspecified+no_connect"))
    )
    (net (code "197") (name "unconnected-(U8-GPB5-Pad6)") (class "Default")
      (node (ref "U8") (pin "6") (pinfunction "GPB5_6") (pintype "unspecified+no_connect"))
    )
    (net (code "198") (name "unconnected-(U8-GPB6-Pad7)") (class "Default")
      (node (ref "U8") (pin "7") (pinfunction "GPB6_7") (pintype "unspecified+no_connect"))
    )
    (net (code "199") (name "unconnected-(U8-GPB7-Pad8)") (class "Default")
      (node (ref "U8") (pin "8") (pinfunction "GPB7_8") (pintype "unspecified+no_connect"))
    )
    (net (code "200") (name "unconnected-(U8-INTA-Pad20)") (class "Default")
      (node (ref "U8") (pin "20") (pinfunction "INTA_20") (pintype "unspecified+no_connect"))
    )
    (net (code "201") (name "unconnected-(U8-INTB-Pad19)") (class "Default")
      (node (ref "U8") (pin "19") (pinfunction "INTB_19") (pintype "unspecified+no_connect"))
    )
    (net (code "202") (name "unconnected-(U8-NC-Pad11)") (class "Default")
      (node (ref "U8") (pin "11") (pinfunction "NC_11") (pintype "unspecified+no_connect"))
    )
    (net (code "203") (name "unconnected-(U8-NC-Pad14)") (class "Default")
      (node (ref "U8") (pin "14") (pinfunction "NC_14") (pintype "unspecified+no_connect"))
    )
    (net (code "204") (name "unconnected-(U10-Pad14)") (class "Default")
      (node (ref "U10") (pin "14") (pinfunction "14_14") (pintype "unspecified+no_connect"))
    )
    (net (code "205") (name "unconnected-(U10-Pad20)") (class "Default")
      (node (ref "U10") (pin "20") (pinfunction "20_20") (pintype "unspecified+no_connect"))
    )
    (net (code "206") (name "unconnected-(U11-Y3-Pad12)") (class "Default")
      (node (ref "U11") (pin "12") (pinfunction "Y3_12") (pintype "unspecified+no_connect"))
    )
    (net (code "207") (name "unconnected-(U11-Y4-Pad11)") (class "Default")
      (node (ref "U11") (pin "11") (pinfunction "Y4_11") (pintype "unspecified+no_connect"))
    )
    (net (code "208") (name "unconnected-(U11-Y5-Pad10)") (class "Default")
      (node (ref "U11") (pin "10") (pinfunction "Y5_10") (pintype "unspecified+no_connect"))
    )
    (net (code "209") (name "unconnected-(U11-Y6-Pad9)") (class "Default")
      (node (ref "U11") (pin "9") (pinfunction "Y6_9") (pintype "unspecified+no_connect"))
    )
    (net (code "210") (name "unconnected-(U11-Y7-Pad7)") (class "Default")
      (node (ref "U11") (pin "7") (pinfunction "Y7_7") (pintype "unspecified+no_connect"))
    )
    (net (code "211") (name "unconnected-(U12-Y3-Pad12)") (class "Default")
      (node (ref "U12") (pin "12") (pinfunction "Y3_12") (pintype "unspecified+no_connect"))
    )
    (net (code "212") (name "unconnected-(U12-Y4-Pad11)") (class "Default")
      (node (ref "U12") (pin "11") (pinfunction "Y4_11") (pintype "unspecified+no_connect"))
    )
    (net (code "213") (name "unconnected-(U12-Y5-Pad10)") (class "Default")
      (node (ref "U12") (pin "10") (pinfunction "Y5_10") (pintype "unspecified+no_connect"))
    )
    (net (code "214") (name "unconnected-(U12-Y6-Pad9)") (class "Default")
      (node (ref "U12") (pin "9") (pinfunction "Y6_9") (pintype "unspecified+no_connect"))
    )
    (net (code "215") (name "unconnected-(U12-Y7-Pad7)") (class "Default")
      (node (ref "U12") (pin "7") (pinfunction "Y7_7") (pintype "unspecified+no_connect"))
    )
    (net (code "216") (name "unconnected-(U13-Y3-Pad12)") (class "Default")
      (node (ref "U13") (pin "12") (pinfunction "Y3_12") (pintype "unspecified+no_connect"))
    )
    (net (code "217") (name "unconnected-(U13-Y4-Pad11)") (class "Default")
      (node (ref "U13") (pin "11") (pinfunction "Y4_11") (pintype "unspecified+no_connect"))
    )
    (net (code "218") (name "unconnected-(U13-Y5-Pad10)") (class "Default")
      (node (ref "U13") (pin "10") (pinfunction "Y5_10") (pintype "unspecified+no_connect"))
    )
    (net (code "219") (name "unconnected-(U13-Y6-Pad9)") (class "Default")
      (node (ref "U13") (pin "9") (pinfunction "Y6_9") (pintype "unspecified+no_connect"))
    )
    (net (code "220") (name "unconnected-(U13-Y7-Pad7)") (class "Default")
      (node (ref "U13") (pin "7") (pinfunction "Y7_7") (pintype "unspecified+no_connect"))
    )
    (net (code "221") (name "unconnected-(VGA-Pad4)") (class "Default")
      (node (ref "VGA") (pin "4") (pinfunction "4_4") (pintype "unspecified+no_connect"))
    )
    (net (code "222") (name "unconnected-(VGA-Pad9)") (class "Default")
      (node (ref "VGA") (pin "9") (pinfunction "9_9") (pintype "unspecified+no_connect"))
    )
    (net (code "223") (name "unconnected-(VGA-Pad11)") (class "Default")
      (node (ref "VGA") (pin "11") (pinfunction "11_11") (pintype "unspecified+no_connect"))
    )
    (net (code "224") (name "unconnected-(VGA-Pad12)") (class "Default")
      (node (ref "VGA") (pin "12") (pinfunction "12_12") (pintype "unspecified+no_connect"))
    )
    (net (code "225") (name "unconnected-(VGA-Pad15)") (class "Default")
      (node (ref "VGA") (pin "15") (pinfunction "15_15") (pintype "unspecified+no_connect"))
    )
    (net (code "226") (name "{slash}BUSACK") (class "Default")
      (node (ref "R6") (pin "1") (pinfunction "1_1") (pintype "unspecified"))
      (node (ref "S1") (pin "62") (pinfunction "/BUSAK_62") (pintype "unspecified"))
      (node (ref "S2") (pin "62") (pinfunction "/BUSAK_62") (pintype "unspecified"))
      (node (ref "S3") (pin "62") (pinfunction "/BUSAK_62") (pintype "unspecified"))
      (node (ref "U1") (pin "23") (pinfunction "/BUSAK_23") (pintype "unspecified"))
    )
    (net (code "227") (name "{slash}EN1") (class "Default")
      (node (ref "S1") (pin "26") (pinfunction "/IORQ_26") (pintype "unspecified"))
      (node (ref "U11") (pin "15") (pinfunction "Y0_15") (pintype "unspecified"))
    )
    (net (code "228") (name "{slash}EN2") (class "Default")
      (node (ref "S2") (pin "26") (pinfunction "/IORQ_26") (pintype "unspecified"))
      (node (ref "U11") (pin "14") (pinfunction "Y1_14") (pintype "unspecified"))
    )
    (net (code "229") (name "{slash}EN3") (class "Default")
      (node (ref "S3") (pin "26") (pinfunction "/IORQ_26") (pintype "unspecified"))
      (node (ref "U11") (pin "13") (pinfunction "Y2_13") (pintype "unspecified"))
    )
    (net (code "230") (name "{slash}HALT") (class "Default")
      (node (ref "R4") (pin "1") (pinfunction "1_1") (pintype "unspecified"))
      (node (ref "S1") (pin "63") (pinfunction "/HALT_63") (pintype "unspecified"))
      (node (ref "S2") (pin "63") (pinfunction "/HALT_63") (pintype "unspecified"))
      (node (ref "S3") (pin "63") (pinfunction "/HALT_63") (pintype "unspecified"))
      (node (ref "U1") (pin "18") (pinfunction "/HALT_18") (pintype "unspecified"))
    )
    (net (code "231") (name "{slash}IORQ") (class "Default")
      (node (ref "R1") (pin "1") (pinfunction "1_1") (pintype "unspecified"))
      (node (ref "U1") (pin "20") (pinfunction "/IORQ_20") (pintype "unspecified"))
      (node (ref "U11") (pin "4") (pinfunction "G2A#_4") (pintype "unspecified"))
      (node (ref "U3") (pin "9") (pinfunction "3A_9") (pintype "unspecified"))
    )
    (net (code "232") (name "{slash}M1") (class "Default")
      (node (ref "S1") (pin "19") (pinfunction "/M1_19") (pintype "unspecified"))
      (node (ref "S2") (pin "19") (pinfunction "/M1_19") (pintype "unspecified"))
      (node (ref "S3") (pin "19") (pinfunction "/M1_19") (pintype "unspecified"))
      (node (ref "U1") (pin "27") (pinfunction "/M1_27") (pintype "unspecified"))
    )
    (net (code "233") (name "{slash}NB_RST") (class "Default")
      (node (ref "C20") (pin "2") (pinfunction "2_2") (pintype "unspecified"))
      (node (ref "D7") (pin "C") (pinfunction "C_C") (pintype "unspecified"))
      (node (ref "JP5") (pin "2") (pinfunction "2_2") (pintype "unspecified"))
      (node (ref "R40") (pin "1") (pinfunction "1_1") (pintype "unspecified"))
      (node (ref "SW2") (pin "1") (pinfunction "1_1") (pintype "unspecified"))
      (node (ref "SW2") (pin "2") (pinfunction "2_2") (pintype "unspecified"))
      (node (ref "U9") (pin "2") (pinfunction "RESET#_2") (pintype "unspecified"))
    )
    (net (code "234") (name "{slash}NMI") (class "Default")
      (node (ref "RP1") (pin "2") (pintype "unspecified"))
      (node (ref "S1") (pin "66") (pinfunction "/NMI_66") (pintype "unspecified"))
      (node (ref "S2") (pin "66") (pinfunction "/NMI_66") (pintype "unspecified"))
      (node (ref "S3") (pin "66") (pinfunction "/NMI_66") (pintype "unspecified"))
      (node (ref "U1") (pin "17") (pinfunction "/NMI_17") (pintype "unspecified"))
    )
    (net (code "235") (name "{slash}PS_ON") (class "Default")
      (node (ref "Q6") (pin "3") (pinfunction "D_3") (pintype "unspecified"))
      (node (ref "R47") (pin "2") (pinfunction "2_2") (pintype "unspecified"))
      (node (ref "U10") (pin "16") (pinfunction "16_16") (pintype "unspecified"))
    )
    (net (code "236") (name "{slash}RD1") (class "Default")
      (node (ref "S1") (pin "25") (pinfunction "/RD_25") (pintype "unspecified"))
      (node (ref "U12") (pin "15") (pinfunction "Y0_15") (pintype "unspecified"))
    )
    (net (code "237") (name "{slash}RD2") (class "Default")
      (node (ref "S2") (pin "25") (pinfunction "/RD_25") (pintype "unspecified"))
      (node (ref "U12") (pin "14") (pinfunction "Y1_14") (pintype "unspecified"))
    )
    (net (code "238") (name "{slash}RD3") (class "Default")
      (node (ref "S3") (pin "25") (pinfunction "/RD_25") (pintype "unspecified"))
      (node (ref "U12") (pin "13") (pinfunction "Y2_13") (pintype "unspecified"))
    )
    (net (code "239") (name "{slash}RFSH") (class "Default")
      (node (ref "S1") (pin "59") (pinfunction "/RFSH_59") (pintype "unspecified"))
      (node (ref "S2") (pin "59") (pinfunction "/RFSH_59") (pintype "unspecified"))
      (node (ref "S3") (pin "59") (pinfunction "/RFSH_59") (pintype "unspecified"))
      (node (ref "U1") (pin "28") (pinfunction "/RFSH_28") (pintype "unspecified"))
    )
    (net (code "240") (name "{slash}SB_RST") (class "Default")
      (node (ref "C19") (pin "2") (pinfunction "2_2") (pintype "unspecified"))
      (node (ref "M1") (pin "16") (pinfunction "RST_16") (pintype "unspecified"))
      (node (ref "U6") (pin "2") (pinfunction "RESET#_2") (pintype "unspecified"))
    )
    (net (code "241") (name "{slash}WR1") (class "Default")
      (node (ref "S1") (pin "24") (pinfunction "/WR_24") (pintype "unspecified"))
      (node (ref "U13") (pin "15") (pinfunction "Y0_15") (pintype "unspecified"))
    )
    (net (code "242") (name "{slash}WR2") (class "Default")
      (node (ref "S2") (pin "24") (pinfunction "/WR_24") (pintype "unspecified"))
      (node (ref "U13") (pin "14") (pinfunction "Y1_14") (pintype "unspecified"))
    )
    (net (code "243") (name "{slash}WR3") (class "Default")
      (node (ref "S3") (pin "24") (pinfunction "/WR_24") (pintype "unspecified"))
      (node (ref "U13") (pin "13") (pinfunction "Y2_13") (pintype "unspecified"))
    )
  )
)
